# 5_3.net
KiCad netlist of a schematic drawn in Altium Designer
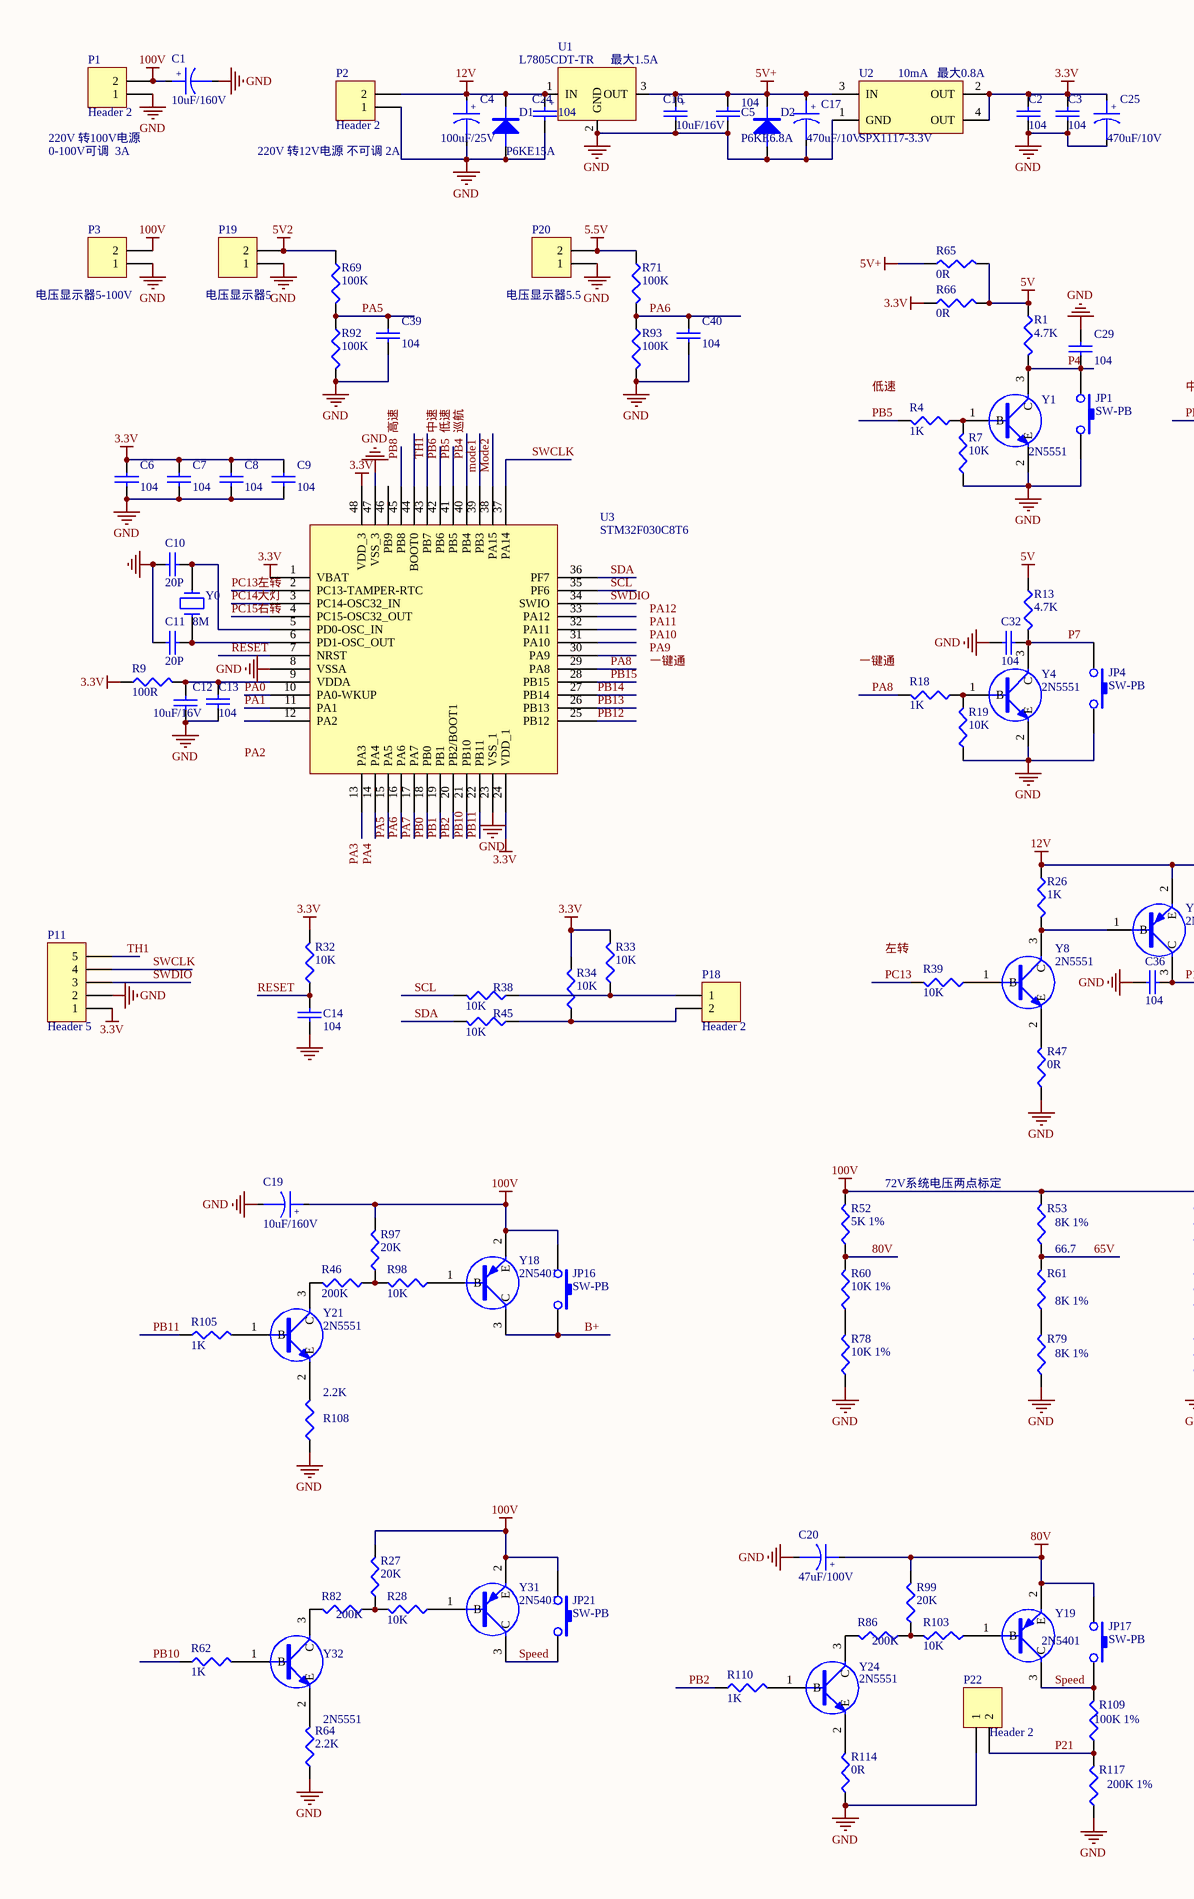
[diagram p0: 仪表自测5.3.SchDoc, left]
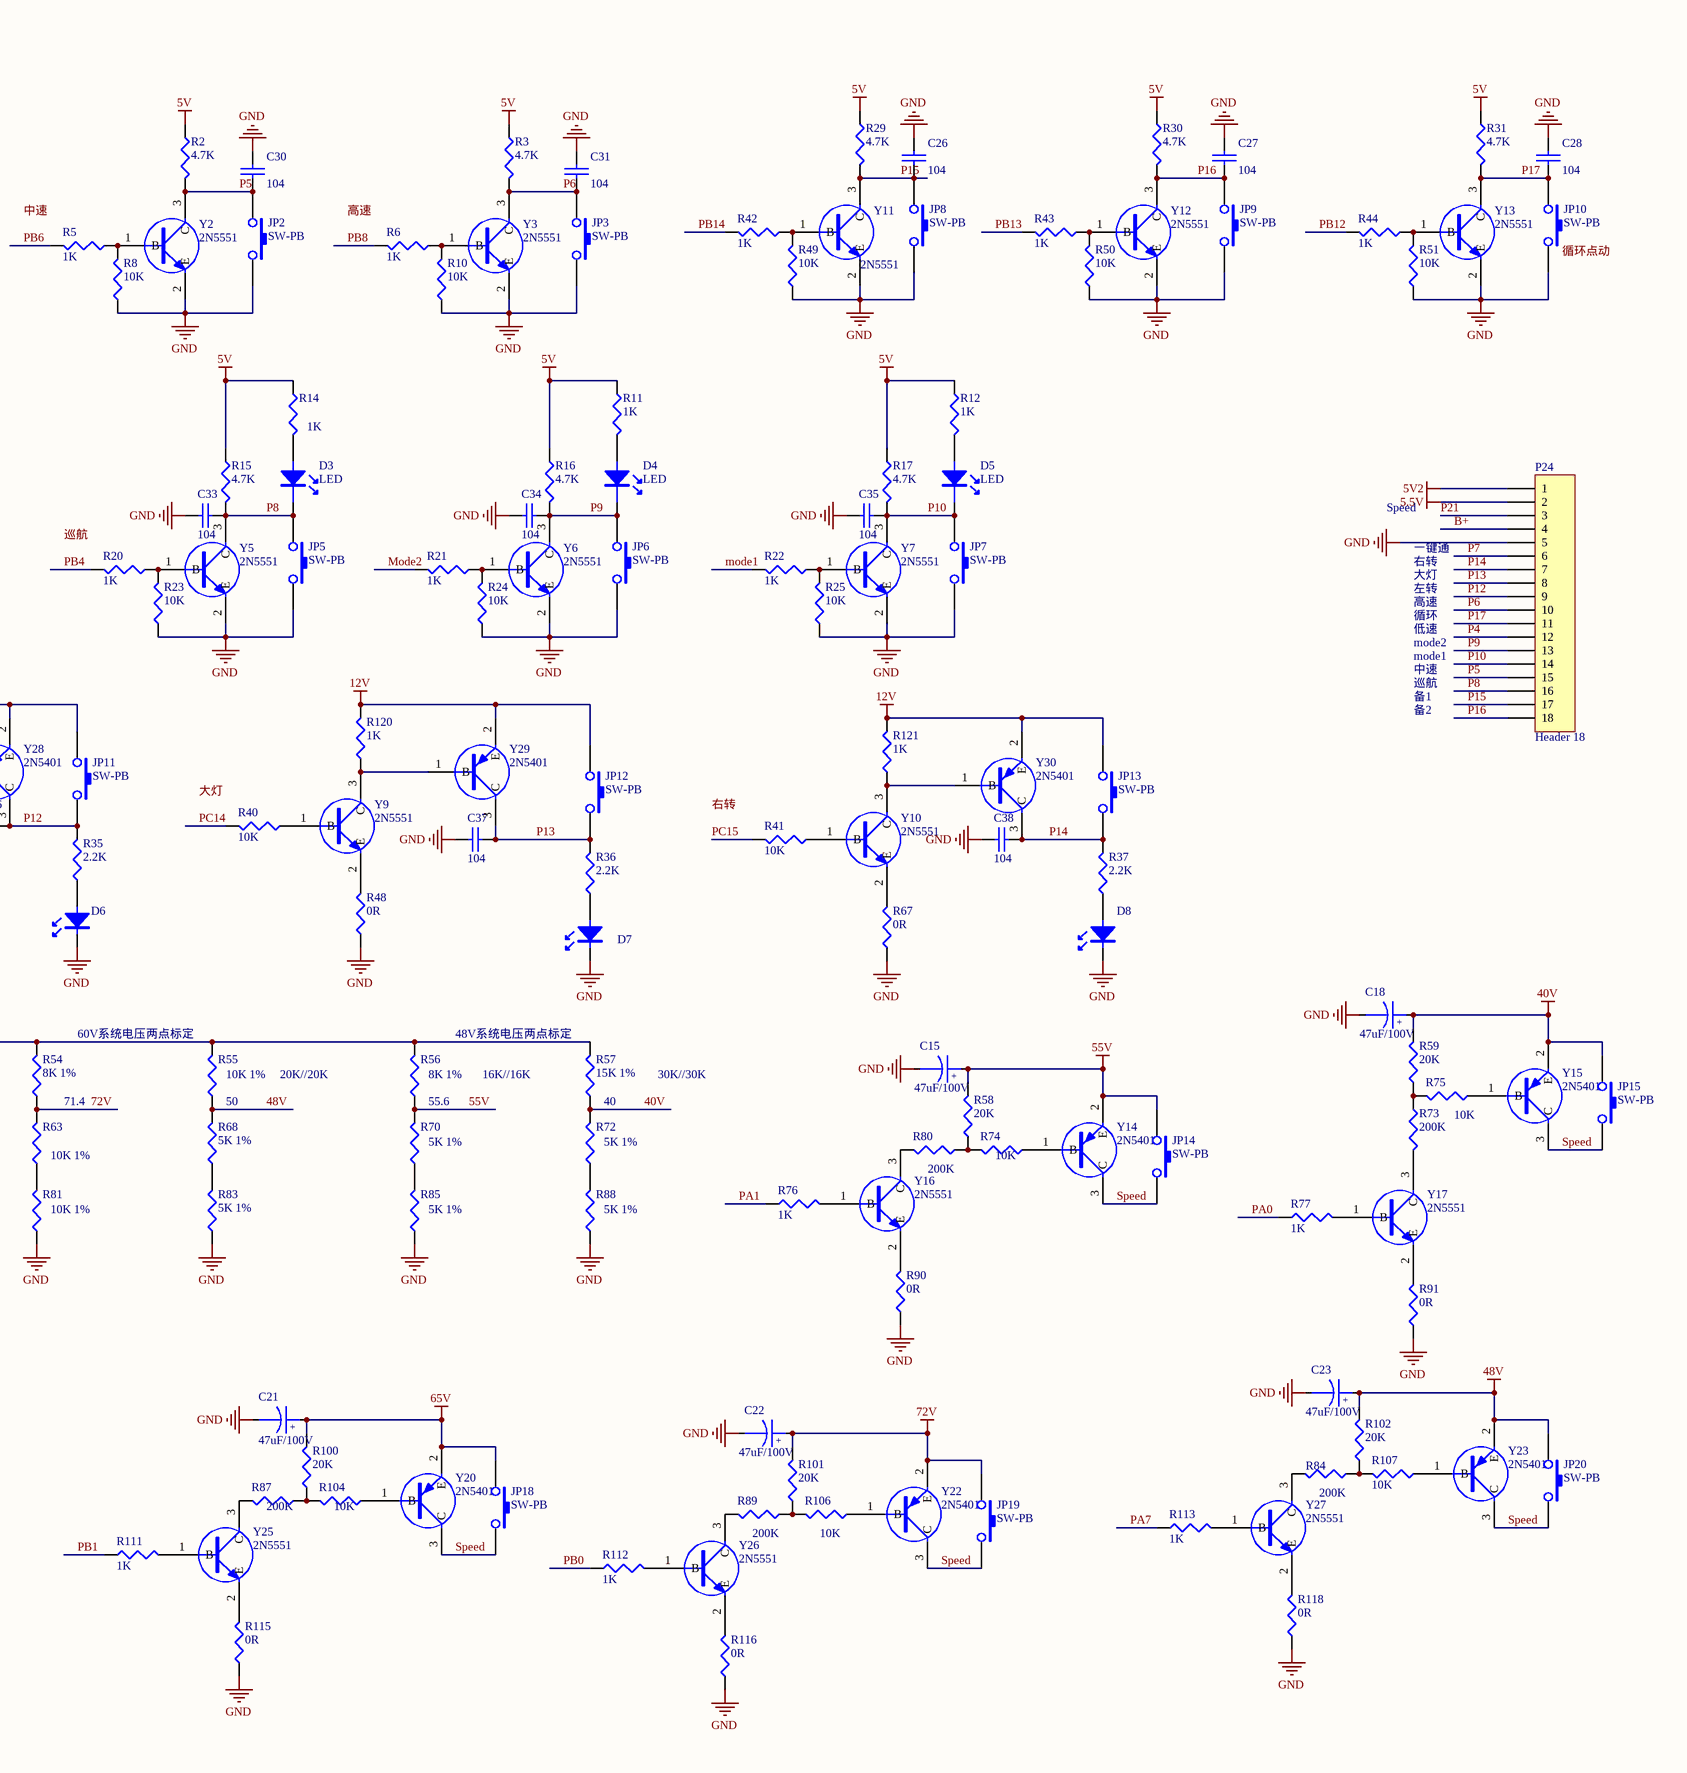
[diagram p1: 仪表自测5.3.SchDoc, right]

(export (version "E")
  (design (tool "Eeschema 10.0.6"))
  (components
    (comp (ref "C1") (value "10uF/160V") (footprint "RB 8*12") (libsource (lib "dsp") (part "Capacitor")))
    (comp (ref "C2") (value "104") (footprint "0805") (libsource (lib "dsp") (part "Cap")))
    (comp (ref "C3") (value "104") (footprint "0805") (libsource (lib "dsp") (part "Cap")))
    (comp (ref "C4") (value "100uF/25V") (footprint "RB.1/.2") (libsource (lib "dsp") (part "Capacitor")))
    (comp (ref "C5") (value "104") (footprint "0805") (libsource (lib "dsp") (part "Cap")))
    (comp (ref "C6")
      (value "104")
      (footprint "0805")
      (description "Capacitor")
      (libsource (lib "*") (part "CAP"))
    )
    (comp (ref "C7")
      (value "104")
      (footprint "0805")
      (description "Capacitor")
      (libsource (lib "*") (part "CAP"))
    )
    (comp (ref "C8")
      (value "104")
      (footprint "0805")
      (description "Capacitor")
      (libsource (lib "*") (part "CAP"))
    )
    (comp (ref "C9")
      (value "104")
      (footprint "0805")
      (description "Capacitor")
      (libsource (lib "*") (part "CAP"))
    )
    (comp (ref "C10")
      (value "20P")
      (footprint "0805")
      (description "Capacitor")
      (libsource (lib "") (part "CAP_1"))
    )
    (comp (ref "C11")
      (value "20P")
      (footprint "0805")
      (description "Capacitor")
      (libsource (lib "") (part "CAP_1"))
    )
    (comp (ref "C12")
      (value "10uF/16V")
      (footprint "1206")
      (description "Capacitor")
      (libsource (lib "*") (part "CAP"))
    )
    (comp (ref "C13")
      (value "104")
      (footprint "0805")
      (description "Capacitor")
      (libsource (lib "*") (part "CAP"))
    )
    (comp (ref "C14") (value "104") (footprint "0805") (libsource (lib "dsp") (part "Cap")))
    (comp (ref "C15") (value "47uF/100V") (footprint "RB 8*12") (libsource (lib "dsp") (part "Capacitor")))
    (comp (ref "C16")
      (value "10uF/16V")
      (footprint "1206")
      (description "Capacitor")
      (libsource (lib "dsp") (part "CAP_1"))
    )
    (comp (ref "C17") (value "470uF/10V") (footprint "RB.1/.2") (libsource (lib "dsp") (part "Capacitor")))
    (comp (ref "C18") (value "47uF/100V") (footprint "RB 8*12") (libsource (lib "dsp") (part "Capacitor")))
    (comp (ref "C19") (value "10uF/160V") (footprint "RB 8*12") (libsource (lib "dsp") (part "Capacitor")))
    (comp (ref "C20") (value "47uF/100V") (footprint "RB 8*12") (libsource (lib "dsp") (part "Capacitor")))
    (comp (ref "C21") (value "47uF/100V") (footprint "RB 8*12") (libsource (lib "dsp") (part "Capacitor")))
    (comp (ref "C22") (value "47uF/100V") (footprint "RB 8*12") (libsource (lib "dsp") (part "Capacitor")))
    (comp (ref "C23") (value "47uF/100V") (footprint "RB 8*12") (libsource (lib "dsp") (part "Capacitor")))
    (comp (ref "C24")
      (value "104")
      (footprint "0805")
      (description "Capacitor")
      (libsource (lib "dsp") (part "CAP_1"))
    )
    (comp (ref "C25") (value "470uF/10V") (footprint "RB.1/.2") (libsource (lib "dsp") (part "Capacitor")))
    (comp (ref "C26") (value "104") (footprint "0805") (libsource (lib "dsp") (part "Cap")))
    (comp (ref "C27") (value "104") (footprint "0805") (libsource (lib "dsp") (part "Cap")))
    (comp (ref "C28") (value "104") (footprint "0805") (libsource (lib "dsp") (part "Cap")))
    (comp (ref "C29") (value "104") (footprint "0805") (libsource (lib "dsp") (part "Cap")))
    (comp (ref "C30") (value "104") (footprint "0805") (libsource (lib "dsp") (part "Cap")))
    (comp (ref "C31") (value "104") (footprint "0805") (libsource (lib "dsp") (part "Cap")))
    (comp (ref "C32") (value "104") (footprint "0805") (libsource (lib "dsp") (part "Cap")))
    (comp (ref "C33") (value "104") (footprint "0805") (libsource (lib "dsp") (part "Cap")))
    (comp (ref "C34") (value "104") (footprint "0805") (libsource (lib "dsp") (part "Cap")))
    (comp (ref "C35") (value "104") (footprint "0805") (libsource (lib "dsp") (part "Cap")))
    (comp (ref "C36") (value "104") (footprint "0805") (libsource (lib "dsp") (part "Cap")))
    (comp (ref "C37") (value "104") (footprint "0805") (libsource (lib "dsp") (part "Cap")))
    (comp (ref "C38") (value "104") (footprint "0805") (libsource (lib "dsp") (part "Cap")))
    (comp (ref "C39")
      (value "104")
      (footprint "0805")
      (description "Capacitor")
      (libsource (lib "*") (part "CAP"))
    )
    (comp (ref "C40")
      (value "104")
      (footprint "0805")
      (description "Capacitor")
      (libsource (lib "*") (part "CAP"))
    )
    (comp (ref "D1")
      (value "P6KE15A")
      (footprint "SMA")
      (description "Diode")
      (libsource (lib "dsp") (part "DIODE"))
    )
    (comp (ref "D2")
      (value "P6KE6.8A")
      (footprint "SMA")
      (description "Diode")
      (libsource (lib "dsp") (part "DIODE"))
    )
    (comp (ref "D3") (value "LED") (footprint "RB.1/.2") (libsource (lib "dsp") (part "LED")))
    (comp (ref "D4") (value "LED") (footprint "RB.1/.2") (libsource (lib "dsp") (part "LED")))
    (comp (ref "D5") (value "LED") (footprint "RB.1/.2") (libsource (lib "dsp") (part "LED")))
    (comp (ref "D6") (value "~") (footprint "RB.1/.2") (libsource (lib "*") (part "LED")))
    (comp (ref "D7") (value "~") (footprint "RB.1/.2") (libsource (lib "*") (part "LED")))
    (comp (ref "D8") (value "~") (footprint "RB.1/.2") (libsource (lib "*") (part "LED")))
    (comp (ref "JP1") (value "SW-PB") (footprint "CON2") (libsource (lib "dsp") (part "SW-PB")))
    (comp (ref "JP2") (value "SW-PB") (footprint "CON2") (libsource (lib "dsp") (part "SW-PB")))
    (comp (ref "JP3") (value "SW-PB") (footprint "CON2") (libsource (lib "dsp") (part "SW-PB")))
    (comp (ref "JP4") (value "SW-PB") (footprint "CON2") (libsource (lib "dsp") (part "SW-PB")))
    (comp (ref "JP5") (value "SW-PB") (footprint "CON2") (libsource (lib "dsp") (part "SW-PB")))
    (comp (ref "JP6") (value "SW-PB") (footprint "CON2") (libsource (lib "dsp") (part "SW-PB")))
    (comp (ref "JP7") (value "SW-PB") (footprint "CON2") (libsource (lib "dsp") (part "SW-PB")))
    (comp (ref "JP8") (value "SW-PB") (footprint "CON2") (libsource (lib "dsp") (part "SW-PB")))
    (comp (ref "JP9") (value "SW-PB") (footprint "CON2") (libsource (lib "dsp") (part "SW-PB")))
    (comp (ref "JP10") (value "SW-PB") (footprint "CON2") (libsource (lib "dsp") (part "SW-PB")))
    (comp (ref "JP11") (value "SW-PB") (footprint "CON2") (libsource (lib "dsp") (part "SW-PB")))
    (comp (ref "JP12") (value "SW-PB") (footprint "CON2") (libsource (lib "dsp") (part "SW-PB")))
    (comp (ref "JP13") (value "SW-PB") (footprint "CON2") (libsource (lib "dsp") (part "SW-PB")))
    (comp (ref "JP14") (value "SW-PB") (footprint "CON2") (libsource (lib "dsp") (part "SW-PB")))
    (comp (ref "JP15") (value "SW-PB") (footprint "CON2") (libsource (lib "dsp") (part "SW-PB")))
    (comp (ref "JP16") (value "SW-PB") (footprint "CON2") (libsource (lib "dsp") (part "SW-PB")))
    (comp (ref "JP17") (value "SW-PB") (footprint "CON2") (libsource (lib "dsp") (part "SW-PB")))
    (comp (ref "JP18") (value "SW-PB") (footprint "CON2") (libsource (lib "dsp") (part "SW-PB")))
    (comp (ref "JP19") (value "SW-PB") (footprint "CON2") (libsource (lib "dsp") (part "SW-PB")))
    (comp (ref "JP20") (value "SW-PB") (footprint "CON2") (libsource (lib "dsp") (part "SW-PB")))
    (comp (ref "JP21") (value "SW-PB") (footprint "CON2") (libsource (lib "dsp") (part "SW-PB")))
    (comp (ref "P1")
      (value "Header 2")
      (footprint "CON2")
      (description "Header, 2-Pin")
      (fields (field (name "PUBLISHER") "Altium Limited"))
      (libsource (lib "Miscellaneous Connectors") (part "Header 2"))
    )
    (comp (ref "P2")
      (value "Header 2")
      (footprint "CON2")
      (description "Header, 2-Pin")
      (fields (field (name "PUBLISHER") "Altium Limited"))
      (libsource (lib "Miscellaneous Connectors") (part "Header 2"))
    )
    (comp (ref "P3")
      (value "电压显示器5-100V")
      (footprint "CON2")
      (description "Header, 2-Pin")
      (fields (field (name "PUBLISHER") "Altium Limited"))
      (libsource (lib "Miscellaneous Connectors") (part "Header 2"))
    )
    (comp (ref "P11")
      (value "Header 5")
      (footprint "HDR1X5")
      (description "Header, 5-Pin")
      (fields (field (name "PUBLISHER") "Altium Limited"))
      (libsource (lib "Miscellaneous Connectors") (part "Header 5"))
    )
    (comp (ref "P18")
      (value "Header 2")
      (footprint "CON2")
      (description "Header, 2-Pin")
      (fields (field (name "PUBLISHER") "Altium Limited"))
      (libsource (lib "") (part "Header 2_1"))
    )
    (comp (ref "P19")
      (value "电压显示器5")
      (footprint "CON2")
      (description "Header, 2-Pin")
      (fields (field (name "PUBLISHER") "Altium Limited"))
      (libsource (lib "Miscellaneous Connectors") (part "Header 2"))
    )
    (comp (ref "P20")
      (value "电压显示器5.5")
      (footprint "CON2")
      (description "Header, 2-Pin")
      (fields (field (name "PUBLISHER") "Altium Limited"))
      (libsource (lib "Miscellaneous Connectors") (part "Header 2"))
    )
    (comp (ref "P22")
      (value "Header 2")
      (footprint "CON2")
      (description "Header, 2-Pin")
      (fields (field (name "PUBLISHER") "Altium Limited"))
      (libsource (lib "dsp") (part "Header 2"))
    )
    (comp (ref "P24")
      (value "Header 18")
      (footprint "SIP18")
      (description "Header, 18-Pin")
      (fields (field (name "PUBLISHER") "Altium Limited"))
      (libsource (lib "dsp") (part "Header 18"))
    )
    (comp (ref "R1") (value "4.7K") (footprint "0805") (libsource (lib "dsp") (part "RES1")))
    (comp (ref "R2") (value "4.7K") (footprint "0805") (libsource (lib "dsp") (part "RES1")))
    (comp (ref "R3") (value "4.7K") (footprint "0805") (libsource (lib "dsp") (part "RES1")))
    (comp (ref "R4") (value "1K") (footprint "0805") (libsource (lib "dsp") (part "RES1")))
    (comp (ref "R5") (value "1K") (footprint "0805") (libsource (lib "dsp") (part "RES1")))
    (comp (ref "R6") (value "1K") (footprint "0805") (libsource (lib "dsp") (part "RES1")))
    (comp (ref "R7") (value "10K") (footprint "0805") (libsource (lib "dsp") (part "RES1")))
    (comp (ref "R8") (value "10K") (footprint "0805") (libsource (lib "dsp") (part "RES1")))
    (comp (ref "R9") (value "100R") (footprint "0805") (libsource (lib "dsp") (part "RES1")))
    (comp (ref "R10") (value "10K") (footprint "0805") (libsource (lib "dsp") (part "RES1")))
    (comp (ref "R11") (value "1K") (footprint "0805") (libsource (lib "dsp") (part "RES1")))
    (comp (ref "R12") (value "1K") (footprint "0805") (libsource (lib "dsp") (part "RES1")))
    (comp (ref "R13") (value "4.7K") (footprint "0805") (libsource (lib "dsp") (part "RES1")))
    (comp (ref "R14") (value "1K") (footprint "0805") (libsource (lib "dsp") (part "RES1")))
    (comp (ref "R15") (value "4.7K") (footprint "0805") (libsource (lib "dsp") (part "RES1")))
    (comp (ref "R16") (value "4.7K") (footprint "0805") (libsource (lib "dsp") (part "RES1")))
    (comp (ref "R17") (value "4.7K") (footprint "0805") (libsource (lib "dsp") (part "RES1")))
    (comp (ref "R18") (value "1K") (footprint "0805") (libsource (lib "dsp") (part "RES1")))
    (comp (ref "R19") (value "10K") (footprint "0805") (libsource (lib "dsp") (part "RES1")))
    (comp (ref "R20") (value "1K") (footprint "0805") (libsource (lib "dsp") (part "RES1")))
    (comp (ref "R21") (value "1K") (footprint "0805") (libsource (lib "dsp") (part "RES1")))
    (comp (ref "R22") (value "1K") (footprint "0805") (libsource (lib "dsp") (part "RES1")))
    (comp (ref "R23") (value "10K") (footprint "0805") (libsource (lib "dsp") (part "RES1")))
    (comp (ref "R24") (value "10K") (footprint "0805") (libsource (lib "dsp") (part "RES1")))
    (comp (ref "R25") (value "10K") (footprint "0805") (libsource (lib "dsp") (part "RES1")))
    (comp (ref "R26") (value "1K") (footprint "0805") (libsource (lib "dsp") (part "RES1")))
    (comp (ref "R27") (value "20K") (footprint "0805") (libsource (lib "dsp") (part "RES1")))
    (comp (ref "R28") (value "10K") (footprint "0805") (libsource (lib "dsp") (part "RES1")))
    (comp (ref "R29") (value "4.7K") (footprint "0805") (libsource (lib "dsp") (part "RES1")))
    (comp (ref "R30") (value "4.7K") (footprint "0805") (libsource (lib "dsp") (part "RES1")))
    (comp (ref "R31") (value "4.7K") (footprint "0805") (libsource (lib "dsp") (part "RES1")))
    (comp (ref "R32") (value "10K") (footprint "0805") (libsource (lib "dsp") (part "RES1")))
    (comp (ref "R33") (value "10K") (footprint "0805") (libsource (lib "dsp") (part "RES1")))
    (comp (ref "R34") (value "10K") (footprint "0805") (libsource (lib "dsp") (part "RES1")))
    (comp (ref "R35") (value "2.2K") (footprint "0805") (libsource (lib "dsp") (part "RES1")))
    (comp (ref "R36") (value "2.2K") (footprint "0805") (libsource (lib "dsp") (part "RES1")))
    (comp (ref "R37") (value "2.2K") (footprint "0805") (libsource (lib "dsp") (part "RES1")))
    (comp (ref "R38") (value "10K") (footprint "0805") (libsource (lib "dsp") (part "RES1")))
    (comp (ref "R39") (value "10K") (footprint "0805") (libsource (lib "dsp") (part "RES1")))
    (comp (ref "R40") (value "10K") (footprint "0805") (libsource (lib "dsp") (part "RES1")))
    (comp (ref "R41") (value "10K") (footprint "0805") (libsource (lib "dsp") (part "RES1")))
    (comp (ref "R42") (value "1K") (footprint "0805") (libsource (lib "dsp") (part "RES1")))
    (comp (ref "R43") (value "1K") (footprint "0805") (libsource (lib "dsp") (part "RES1")))
    (comp (ref "R44") (value "1K") (footprint "0805") (libsource (lib "dsp") (part "RES1")))
    (comp (ref "R45") (value "10K") (footprint "0805") (libsource (lib "dsp") (part "RES1")))
    (comp (ref "R46") (value "200K") (footprint "0805") (libsource (lib "dsp") (part "RES1")))
    (comp (ref "R47") (value "0R") (footprint "0805") (libsource (lib "dsp") (part "RES1")))
    (comp (ref "R48") (value "0R") (footprint "0805") (libsource (lib "dsp") (part "RES1")))
    (comp (ref "R49") (value "10K") (footprint "0805") (libsource (lib "dsp") (part "RES1")))
    (comp (ref "R50") (value "10K") (footprint "0805") (libsource (lib "dsp") (part "RES1")))
    (comp (ref "R51") (value "10K") (footprint "0805") (libsource (lib "dsp") (part "RES1")))
    (comp (ref "R52") (value "5K 1%") (footprint "1206") (libsource (lib "dsp") (part "RES1")))
    (comp (ref "R53") (value "8K 1%") (footprint "1206") (libsource (lib "dsp") (part "RES1")))
    (comp (ref "R54") (value "8K 1%") (footprint "1206") (libsource (lib "dsp") (part "RES1")))
    (comp (ref "R55") (value "10K 1%") (footprint "1206") (libsource (lib "dsp") (part "RES1")))
    (comp (ref "R56") (value "8K 1%") (footprint "1206") (libsource (lib "dsp") (part "RES1")))
    (comp (ref "R57") (value "15K 1%") (footprint "1206") (libsource (lib "dsp") (part "RES1")))
    (comp (ref "R58") (value "20K") (footprint "0805") (libsource (lib "dsp") (part "RES1")))
    (comp (ref "R59") (value "20K") (footprint "0805") (libsource (lib "dsp") (part "RES1")))
    (comp (ref "R60") (value "10K 1%") (footprint "1206") (libsource (lib "dsp") (part "RES1")))
    (comp (ref "R61") (value "8K 1%") (footprint "1206") (libsource (lib "dsp") (part "RES1")))
    (comp (ref "R62") (value "1K") (footprint "0805") (libsource (lib "dsp") (part "RES1")))
    (comp (ref "R63") (value "10K 1%") (footprint "1206") (libsource (lib "dsp") (part "RES1")))
    (comp (ref "R64") (value "2.2K") (footprint "0805") (libsource (lib "dsp") (part "RES1")))
    (comp (ref "R65") (value "0R") (footprint "0805") (libsource (lib "dsp") (part "RES1")))
    (comp (ref "R66") (value "0R") (footprint "0805") (libsource (lib "dsp") (part "RES1")))
    (comp (ref "R67") (value "0R") (footprint "0805") (libsource (lib "dsp") (part "RES1")))
    (comp (ref "R68") (value "5K 1%") (footprint "1206") (libsource (lib "dsp") (part "RES1")))
    (comp (ref "R69") (value "100K") (footprint "0805") (libsource (lib "dsp") (part "RES1")))
    (comp (ref "R70") (value "5K 1%") (footprint "1206") (libsource (lib "dsp") (part "RES1")))
    (comp (ref "R71") (value "100K") (footprint "0805") (libsource (lib "dsp") (part "RES1")))
    (comp (ref "R72") (value "5K 1%") (footprint "1206") (libsource (lib "dsp") (part "RES1")))
    (comp (ref "R73") (value "200K") (footprint "0805") (libsource (lib "dsp") (part "RES1")))
    (comp (ref "R74") (value "10K") (footprint "0805") (libsource (lib "dsp") (part "RES1")))
    (comp (ref "R75") (value "10K") (footprint "0805") (libsource (lib "dsp") (part "RES1")))
    (comp (ref "R76") (value "1K") (footprint "0805") (libsource (lib "dsp") (part "RES1")))
    (comp (ref "R77") (value "1K") (footprint "0805") (libsource (lib "dsp") (part "RES1")))
    (comp (ref "R78") (value "10K 1%") (footprint "1206") (libsource (lib "dsp") (part "RES1")))
    (comp (ref "R79") (value "8K 1%") (footprint "1206") (libsource (lib "dsp") (part "RES1")))
    (comp (ref "R80") (value "200K") (footprint "0805") (libsource (lib "dsp") (part "RES1")))
    (comp (ref "R81") (value "10K 1%") (footprint "1206") (libsource (lib "dsp") (part "RES1")))
    (comp (ref "R82") (value "200K") (footprint "0805") (libsource (lib "dsp") (part "RES1")))
    (comp (ref "R83") (value "5K 1%") (footprint "1206") (libsource (lib "dsp") (part "RES1")))
    (comp (ref "R84") (value "200K") (footprint "0805") (libsource (lib "dsp") (part "RES1")))
    (comp (ref "R85") (value "5K 1%") (footprint "1206") (libsource (lib "dsp") (part "RES1")))
    (comp (ref "R86") (value "200K") (footprint "0805") (libsource (lib "dsp") (part "RES1")))
    (comp (ref "R87") (value "200K") (footprint "0805") (libsource (lib "dsp") (part "RES1")))
    (comp (ref "R88") (value "5K 1%") (footprint "1206") (libsource (lib "dsp") (part "RES1")))
    (comp (ref "R89") (value "200K") (footprint "0805") (libsource (lib "dsp") (part "RES1")))
    (comp (ref "R90") (value "0R") (footprint "0805") (libsource (lib "dsp") (part "RES1")))
    (comp (ref "R91") (value "0R") (footprint "0805") (libsource (lib "dsp") (part "RES1")))
    (comp (ref "R92") (value "100K") (footprint "0805") (libsource (lib "dsp") (part "RES1")))
    (comp (ref "R93") (value "100K") (footprint "0805") (libsource (lib "dsp") (part "RES1")))
    (comp (ref "R97") (value "20K") (footprint "0805") (libsource (lib "dsp") (part "RES1")))
    (comp (ref "R98") (value "10K") (footprint "0805") (libsource (lib "dsp") (part "RES1")))
    (comp (ref "R99") (value "20K") (footprint "0805") (libsource (lib "dsp") (part "RES1")))
    (comp (ref "R100") (value "20K") (footprint "0805") (libsource (lib "dsp") (part "RES1")))
    (comp (ref "R101") (value "20K") (footprint "0805") (libsource (lib "dsp") (part "RES1")))
    (comp (ref "R102") (value "20K") (footprint "0805") (libsource (lib "dsp") (part "RES1")))
    (comp (ref "R103") (value "10K") (footprint "0805") (libsource (lib "dsp") (part "RES1")))
    (comp (ref "R104") (value "10K") (footprint "0805") (libsource (lib "dsp") (part "RES1")))
    (comp (ref "R105") (value "1K") (footprint "0805") (libsource (lib "dsp") (part "RES1")))
    (comp (ref "R106") (value "10K") (footprint "0805") (libsource (lib "dsp") (part "RES1")))
    (comp (ref "R107") (value "10K") (footprint "0805") (libsource (lib "dsp") (part "RES1")))
    (comp (ref "R108") (value "2.2K") (footprint "0805") (libsource (lib "dsp") (part "RES1")))
    (comp (ref "R109") (value "100K 1%") (footprint "2512") (libsource (lib "dsp") (part "RES1")))
    (comp (ref "R110") (value "1K") (footprint "0805") (libsource (lib "dsp") (part "RES1")))
    (comp (ref "R111") (value "1K") (footprint "0805") (libsource (lib "dsp") (part "RES1")))
    (comp (ref "R112") (value "1K") (footprint "0805") (libsource (lib "dsp") (part "RES1")))
    (comp (ref "R113") (value "1K") (footprint "0805") (libsource (lib "dsp") (part "RES1")))
    (comp (ref "R114") (value "0R") (footprint "0805") (libsource (lib "dsp") (part "RES1")))
    (comp (ref "R115") (value "0R") (footprint "0805") (libsource (lib "dsp") (part "RES1")))
    (comp (ref "R116") (value "0R") (footprint "0805") (libsource (lib "dsp") (part "RES1")))
    (comp (ref "R117") (value "200K 1%") (footprint "2512") (libsource (lib "dsp") (part "RES1")))
    (comp (ref "R118") (value "0R") (footprint "0805") (libsource (lib "dsp") (part "RES1")))
    (comp (ref "R120") (value "1K") (footprint "0805") (libsource (lib "dsp") (part "RES1")))
    (comp (ref "R121") (value "1K") (footprint "0805") (libsource (lib "dsp") (part "RES1")))
    (comp (ref "U1") (value "L7805CDT-TR") (footprint "TO-252") (libsource (lib "*") (part "IC3")))
    (comp (ref "U2")
      (value "SPX1117-3.3V")
      (footprint "SOT-223")
      (libsource (lib "dsp") (part "SPX1117-3.3V"))
    )
    (comp (ref "U3")
      (value "STM32F030C8T6")
      (footprint "STM32F103-LQFP48")
      (libsource (lib "dsp") (part "STM32F030C8T6"))
    )
    (comp (ref "Y0")
      (value "8M")
      (footprint "RAD0.2")
      (description "Crystal")
      (libsource (lib "*") (part "CRYSTAL"))
    )
    (comp (ref "Y1")
      (value "2N5551")
      (footprint "SOT-23")
      (description "NPN SOT-23")
      (libsource (lib "dsp") (part "NPN SOT-23"))
    )
    (comp (ref "Y2")
      (value "2N5551")
      (footprint "SOT-23")
      (description "NPN SOT-23")
      (libsource (lib "dsp") (part "NPN SOT-23"))
    )
    (comp (ref "Y3")
      (value "2N5551")
      (footprint "SOT-23")
      (description "NPN SOT-23")
      (libsource (lib "dsp") (part "NPN SOT-23"))
    )
    (comp (ref "Y4")
      (value "2N5551")
      (footprint "SOT-23")
      (description "NPN SOT-23")
      (libsource (lib "dsp") (part "NPN SOT-23"))
    )
    (comp (ref "Y5")
      (value "2N5551")
      (footprint "SOT-23")
      (description "NPN SOT-23")
      (libsource (lib "dsp") (part "NPN SOT-23"))
    )
    (comp (ref "Y6")
      (value "2N5551")
      (footprint "SOT-23")
      (description "NPN SOT-23")
      (libsource (lib "dsp") (part "NPN SOT-23"))
    )
    (comp (ref "Y7")
      (value "2N5551")
      (footprint "SOT-23")
      (description "NPN SOT-23")
      (libsource (lib "dsp") (part "NPN SOT-23"))
    )
    (comp (ref "Y8")
      (value "2N5551")
      (footprint "SOT-23")
      (description "NPN SOT-23")
      (libsource (lib "dsp") (part "NPN SOT-23"))
    )
    (comp (ref "Y9")
      (value "2N5551")
      (footprint "SOT-23")
      (description "NPN SOT-23")
      (libsource (lib "dsp") (part "NPN SOT-23"))
    )
    (comp (ref "Y10")
      (value "2N5551")
      (footprint "SOT-23")
      (description "NPN SOT-23")
      (libsource (lib "dsp") (part "NPN SOT-23"))
    )
    (comp (ref "Y11")
      (value "2N5551")
      (footprint "SOT-23")
      (description "NPN SOT-23")
      (libsource (lib "dsp") (part "NPN SOT-23"))
    )
    (comp (ref "Y12")
      (value "2N5551")
      (footprint "SOT-23")
      (description "NPN SOT-23")
      (libsource (lib "dsp") (part "NPN SOT-23"))
    )
    (comp (ref "Y13")
      (value "2N5551")
      (footprint "SOT-23")
      (description "NPN SOT-23")
      (libsource (lib "dsp") (part "NPN SOT-23"))
    )
    (comp (ref "Y14")
      (value "2N5401")
      (footprint "SOT-23")
      (description "PNP SOT-23")
      (libsource (lib "dsp") (part "PNP SOT-23"))
    )
    (comp (ref "Y15")
      (value "2N5401")
      (footprint "SOT-23")
      (description "PNP SOT-23")
      (libsource (lib "dsp") (part "PNP SOT-23"))
    )
    (comp (ref "Y16")
      (value "2N5551")
      (footprint "SOT-23")
      (description "NPN SOT-23")
      (libsource (lib "dsp") (part "NPN SOT-23"))
    )
    (comp (ref "Y17")
      (value "2N5551")
      (footprint "SOT-23")
      (description "NPN SOT-23")
      (libsource (lib "dsp") (part "NPN SOT-23"))
    )
    (comp (ref "Y18")
      (value "2N5401")
      (footprint "SOT-23")
      (description "PNP SOT-23")
      (libsource (lib "dsp") (part "PNP SOT-23"))
    )
    (comp (ref "Y19")
      (value "2N5401")
      (footprint "SOT-23")
      (description "PNP SOT-23")
      (libsource (lib "dsp") (part "PNP SOT-23"))
    )
    (comp (ref "Y20")
      (value "2N5401")
      (footprint "SOT-23")
      (description "PNP SOT-23")
      (libsource (lib "dsp") (part "PNP SOT-23"))
    )
    (comp (ref "Y21")
      (value "2N5551")
      (footprint "SOT-23")
      (description "NPN SOT-23")
      (libsource (lib "dsp") (part "NPN SOT-23"))
    )
    (comp (ref "Y22")
      (value "2N5401")
      (footprint "SOT-23")
      (description "PNP SOT-23")
      (libsource (lib "dsp") (part "PNP SOT-23"))
    )
    (comp (ref "Y23")
      (value "2N5401")
      (footprint "SOT-23")
      (description "PNP SOT-23")
      (libsource (lib "dsp") (part "PNP SOT-23"))
    )
    (comp (ref "Y24")
      (value "2N5551")
      (footprint "SOT-23")
      (description "NPN SOT-23")
      (libsource (lib "dsp") (part "NPN SOT-23"))
    )
    (comp (ref "Y25")
      (value "2N5551")
      (footprint "SOT-23")
      (description "NPN SOT-23")
      (libsource (lib "dsp") (part "NPN SOT-23"))
    )
    (comp (ref "Y26")
      (value "2N5551")
      (footprint "SOT-23")
      (description "NPN SOT-23")
      (libsource (lib "dsp") (part "NPN SOT-23"))
    )
    (comp (ref "Y27")
      (value "2N5551")
      (footprint "SOT-23")
      (description "NPN SOT-23")
      (libsource (lib "dsp") (part "NPN SOT-23"))
    )
    (comp (ref "Y28")
      (value "2N5401")
      (footprint "SOT-23")
      (description "PNP SOT-23")
      (libsource (lib "dsp") (part "PNP SOT-23"))
    )
    (comp (ref "Y29")
      (value "2N5401")
      (footprint "SOT-23")
      (description "PNP SOT-23")
      (libsource (lib "dsp") (part "PNP SOT-23"))
    )
    (comp (ref "Y30")
      (value "2N5401")
      (footprint "SOT-23")
      (description "PNP SOT-23")
      (libsource (lib "dsp") (part "PNP SOT-23"))
    )
    (comp (ref "Y31")
      (value "2N5401")
      (footprint "SOT-23")
      (description "PNP SOT-23")
      (libsource (lib "dsp") (part "PNP SOT-23"))
    )
    (comp (ref "Y32")
      (value "2N5551")
      (footprint "SOT-23")
      (description "NPN SOT-23")
      (libsource (lib "dsp") (part "NPN SOT-23"))
    )
  )
  (nets
    (net (code "1") (name "/B+") (class "Default")
      (node (ref "JP16") (pin "2") (pinfunction "2_2") (pintype "passive"))
      (node (ref "P24") (pin "4") (pinfunction "4_4") (pintype "passive"))
      (node (ref "Y18") (pin "3") (pinfunction "C_3") (pintype "passive"))
    )
    (net (code "2") (name "/Mode2") (class "Default")
      (node (ref "R21") (pin "2") (pinfunction "2_2") (pintype "passive"))
      (node (ref "U3") (pin "38") (pinfunction "PA15_38") (pintype "passive"))
    )
    (net (code "3") (name "/P4") (class "Default")
      (node (ref "C29") (pin "2") (pinfunction "2_2") (pintype "passive"))
      (node (ref "JP1") (pin "1") (pinfunction "1_1") (pintype "passive"))
      (node (ref "P24") (pin "12") (pinfunction "12_12") (pintype "passive"))
      (node (ref "R1") (pin "2") (pinfunction "2_2") (pintype "passive"))
      (node (ref "Y1") (pin "3") (pinfunction "C_3") (pintype "passive"))
    )
    (net (code "4") (name "/P5") (class "Default")
      (node (ref "C30") (pin "2") (pinfunction "2_2") (pintype "passive"))
      (node (ref "JP2") (pin "1") (pinfunction "1_1") (pintype "passive"))
      (node (ref "P24") (pin "15") (pinfunction "15_15") (pintype "passive"))
      (node (ref "R2") (pin "2") (pinfunction "2_2") (pintype "passive"))
      (node (ref "Y2") (pin "3") (pinfunction "C_3") (pintype "passive"))
    )
    (net (code "5") (name "/P6") (class "Default")
      (node (ref "C31") (pin "2") (pinfunction "2_2") (pintype "passive"))
      (node (ref "JP3") (pin "1") (pinfunction "1_1") (pintype "passive"))
      (node (ref "P24") (pin "10") (pinfunction "10_10") (pintype "passive"))
      (node (ref "R3") (pin "2") (pinfunction "2_2") (pintype "passive"))
      (node (ref "Y3") (pin "3") (pinfunction "C_3") (pintype "passive"))
    )
    (net (code "6") (name "/P7") (class "Default")
      (node (ref "C32") (pin "2") (pinfunction "2_2") (pintype "passive"))
      (node (ref "JP4") (pin "1") (pinfunction "1_1") (pintype "passive"))
      (node (ref "P24") (pin "6") (pinfunction "6_6") (pintype "passive"))
      (node (ref "R13") (pin "2") (pinfunction "2_2") (pintype "passive"))
      (node (ref "Y4") (pin "3") (pinfunction "C_3") (pintype "passive"))
    )
    (net (code "7") (name "/P8") (class "Default")
      (node (ref "C33") (pin "2") (pinfunction "2_2") (pintype "passive"))
      (node (ref "D3") (pin "2") (pinfunction "2_2") (pintype "passive"))
      (node (ref "JP5") (pin "1") (pinfunction "1_1") (pintype "passive"))
      (node (ref "P24") (pin "16") (pinfunction "16_16") (pintype "passive"))
      (node (ref "R15") (pin "2") (pinfunction "2_2") (pintype "passive"))
      (node (ref "Y5") (pin "3") (pinfunction "C_3") (pintype "passive"))
    )
    (net (code "8") (name "/P9") (class "Default")
      (node (ref "C34") (pin "2") (pinfunction "2_2") (pintype "passive"))
      (node (ref "D4") (pin "2") (pinfunction "2_2") (pintype "passive"))
      (node (ref "JP6") (pin "1") (pinfunction "1_1") (pintype "passive"))
      (node (ref "P24") (pin "13") (pinfunction "13_13") (pintype "passive"))
      (node (ref "R16") (pin "2") (pinfunction "2_2") (pintype "passive"))
      (node (ref "Y6") (pin "3") (pinfunction "C_3") (pintype "passive"))
    )
    (net (code "9") (name "/P10") (class "Default")
      (node (ref "C35") (pin "2") (pinfunction "2_2") (pintype "passive"))
      (node (ref "D5") (pin "2") (pinfunction "2_2") (pintype "passive"))
      (node (ref "JP7") (pin "1") (pinfunction "1_1") (pintype "passive"))
      (node (ref "P24") (pin "14") (pinfunction "14_14") (pintype "passive"))
      (node (ref "R17") (pin "2") (pinfunction "2_2") (pintype "passive"))
      (node (ref "Y7") (pin "3") (pinfunction "C_3") (pintype "passive"))
    )
    (net (code "10") (name "/P12") (class "Default")
      (node (ref "C36") (pin "2") (pinfunction "2_2") (pintype "passive"))
      (node (ref "JP11") (pin "2") (pinfunction "2_2") (pintype "passive"))
      (node (ref "P24") (pin "9") (pinfunction "9_9") (pintype "passive"))
      (node (ref "R35") (pin "2") (pinfunction "2_2") (pintype "passive"))
      (node (ref "Y28") (pin "3") (pinfunction "C_3") (pintype "passive"))
    )
    (net (code "11") (name "/P13") (class "Default")
      (node (ref "C37") (pin "2") (pinfunction "2_2") (pintype "passive"))
      (node (ref "JP12") (pin "2") (pinfunction "2_2") (pintype "passive"))
      (node (ref "P24") (pin "8") (pinfunction "8_8") (pintype "passive"))
      (node (ref "R36") (pin "2") (pinfunction "2_2") (pintype "passive"))
      (node (ref "Y29") (pin "3") (pinfunction "C_3") (pintype "passive"))
    )
    (net (code "12") (name "/P14") (class "Default")
      (node (ref "C38") (pin "2") (pinfunction "2_2") (pintype "passive"))
      (node (ref "JP13") (pin "2") (pinfunction "2_2") (pintype "passive"))
      (node (ref "P24") (pin "7") (pinfunction "7_7") (pintype "passive"))
      (node (ref "R37") (pin "2") (pinfunction "2_2") (pintype "passive"))
      (node (ref "Y30") (pin "3") (pinfunction "C_3") (pintype "passive"))
    )
    (net (code "13") (name "/P15") (class "Default")
      (node (ref "C26") (pin "2") (pinfunction "2_2") (pintype "passive"))
      (node (ref "JP8") (pin "1") (pinfunction "1_1") (pintype "passive"))
      (node (ref "P24") (pin "17") (pinfunction "17_17") (pintype "passive"))
      (node (ref "R29") (pin "2") (pinfunction "2_2") (pintype "passive"))
      (node (ref "Y11") (pin "3") (pinfunction "C_3") (pintype "passive"))
    )
    (net (code "14") (name "/P16") (class "Default")
      (node (ref "C27") (pin "2") (pinfunction "2_2") (pintype "passive"))
      (node (ref "JP9") (pin "1") (pinfunction "1_1") (pintype "passive"))
      (node (ref "P24") (pin "18") (pinfunction "18_18") (pintype "passive"))
      (node (ref "R30") (pin "2") (pinfunction "2_2") (pintype "passive"))
      (node (ref "Y12") (pin "3") (pinfunction "C_3") (pintype "passive"))
    )
    (net (code "15") (name "/P17") (class "Default")
      (node (ref "C28") (pin "2") (pinfunction "2_2") (pintype "passive"))
      (node (ref "JP10") (pin "1") (pinfunction "1_1") (pintype "passive"))
      (node (ref "P24") (pin "11") (pinfunction "11_11") (pintype "passive"))
      (node (ref "R31") (pin "2") (pinfunction "2_2") (pintype "passive"))
      (node (ref "Y13") (pin "3") (pinfunction "C_3") (pintype "passive"))
    )
    (net (code "16") (name "/P21") (class "Default")
      (node (ref "P22") (pin "2") (pinfunction "2_2") (pintype "passive"))
      (node (ref "P24") (pin "3") (pinfunction "3_3") (pintype "passive"))
      (node (ref "R109") (pin "1") (pinfunction "1_1") (pintype "passive"))
      (node (ref "R117") (pin "2") (pinfunction "2_2") (pintype "passive"))
    )
    (net (code "17") (name "/PA0") (class "Default")
      (node (ref "R77") (pin "1") (pinfunction "1_1") (pintype "passive"))
      (node (ref "U3") (pin "10") (pinfunction "PA0-WKUP_10") (pintype "passive"))
    )
    (net (code "18") (name "/PA1") (class "Default")
      (node (ref "R76") (pin "1") (pinfunction "1_1") (pintype "passive"))
      (node (ref "U3") (pin "11") (pinfunction "PA1_11") (pintype "passive"))
    )
    (net (code "22") (name "/PA5") (class "Default")
      (node (ref "C39") (pin "2") (pinfunction "2_2") (pintype "passive"))
      (node (ref "R69") (pin "2") (pinfunction "2_2") (pintype "passive"))
      (node (ref "R92") (pin "1") (pinfunction "1_1") (pintype "passive"))
      (node (ref "U3") (pin "15") (pinfunction "PA5_15") (pintype "passive"))
    )
    (net (code "23") (name "/PA6") (class "Default")
      (node (ref "C40") (pin "2") (pinfunction "2_2") (pintype "passive"))
      (node (ref "R71") (pin "2") (pinfunction "2_2") (pintype "passive"))
      (node (ref "R93") (pin "1") (pinfunction "1_1") (pintype "passive"))
      (node (ref "U3") (pin "16") (pinfunction "PA6_16") (pintype "passive"))
    )
    (net (code "24") (name "/PA7") (class "Default")
      (node (ref "R113") (pin "1") (pinfunction "1_1") (pintype "passive"))
      (node (ref "U3") (pin "17") (pinfunction "PA7_17") (pintype "passive"))
    )
    (net (code "25") (name "/PA8") (class "Default")
      (node (ref "R18") (pin "2") (pinfunction "2_2") (pintype "passive"))
      (node (ref "U3") (pin "29") (pinfunction "PA8_29") (pintype "passive"))
    )
    (net (code "30") (name "/PB0") (class "Default")
      (node (ref "R112") (pin "1") (pinfunction "1_1") (pintype "passive"))
      (node (ref "U3") (pin "18") (pinfunction "PB0_18") (pintype "passive"))
    )
    (net (code "31") (name "/PB1") (class "Default")
      (node (ref "R111") (pin "1") (pinfunction "1_1") (pintype "passive"))
      (node (ref "U3") (pin "19") (pinfunction "PB1_19") (pintype "passive"))
    )
    (net (code "32") (name "/PB2") (class "Default")
      (node (ref "R110") (pin "1") (pinfunction "1_1") (pintype "passive"))
      (node (ref "U3") (pin "20") (pinfunction "PB2/BOOT1_20") (pintype "passive"))
    )
    (net (code "33") (name "/PB4") (class "Default")
      (node (ref "R20") (pin "2") (pinfunction "2_2") (pintype "passive"))
      (node (ref "U3") (pin "40") (pinfunction "PB4_40") (pintype "passive"))
    )
    (net (code "34") (name "/PB5") (class "Default")
      (node (ref "R4") (pin "2") (pinfunction "2_2") (pintype "passive"))
      (node (ref "U3") (pin "41") (pinfunction "PB5_41") (pintype "passive"))
    )
    (net (code "35") (name "/PB6") (class "Default")
      (node (ref "R5") (pin "2") (pinfunction "2_2") (pintype "passive"))
      (node (ref "U3") (pin "42") (pinfunction "PB6_42") (pintype "passive"))
    )
    (net (code "36") (name "/PB8") (class "Default")
      (node (ref "R6") (pin "2") (pinfunction "2_2") (pintype "passive"))
      (node (ref "U3") (pin "45") (pinfunction "PB8_45") (pintype "passive"))
    )
    (net (code "37") (name "/PB10") (class "Default")
      (node (ref "R62") (pin "1") (pinfunction "1_1") (pintype "passive"))
      (node (ref "U3") (pin "21") (pinfunction "PB10_21") (pintype "passive"))
    )
    (net (code "38") (name "/PB11") (class "Default")
      (node (ref "R105") (pin "1") (pinfunction "1_1") (pintype "passive"))
      (node (ref "U3") (pin "22") (pinfunction "PB11_22") (pintype "passive"))
    )
    (net (code "39") (name "/PB12") (class "Default")
      (node (ref "R44") (pin "2") (pinfunction "2_2") (pintype "passive"))
      (node (ref "U3") (pin "25") (pinfunction "PB12_25") (pintype "passive"))
    )
    (net (code "40") (name "/PB13") (class "Default")
      (node (ref "R43") (pin "2") (pinfunction "2_2") (pintype "passive"))
      (node (ref "U3") (pin "26") (pinfunction "PB13_26") (pintype "passive"))
    )
    (net (code "41") (name "/PB14") (class "Default")
      (node (ref "R42") (pin "2") (pinfunction "2_2") (pintype "passive"))
      (node (ref "U3") (pin "27") (pinfunction "PB14_27") (pintype "passive"))
    )
    (net (code "42") (name "/PB15") (class "Default")
      (node (ref "U3") (pin "28") (pinfunction "PB15_28") (pintype "passive"))
    )
    (net (code "43") (name "/PC13") (class "Default")
      (node (ref "R39") (pin "2") (pinfunction "2_2") (pintype "passive"))
      (node (ref "U3") (pin "2") (pinfunction "PC13-TAMPER-RTC_2") (pintype "passive"))
    )
    (net (code "44") (name "/PC14") (class "Default")
      (node (ref "R40") (pin "2") (pinfunction "2_2") (pintype "passive"))
      (node (ref "U3") (pin "3") (pinfunction "PC14-OSC32_IN_3") (pintype "passive"))
    )
    (net (code "45") (name "/PC15") (class "Default")
      (node (ref "R41") (pin "2") (pinfunction "2_2") (pintype "passive"))
      (node (ref "U3") (pin "4") (pinfunction "PC15-OSC32_OUT_4") (pintype "passive"))
    )
    (net (code "46") (name "/RESET") (class "Default")
      (node (ref "C14") (pin "1") (pinfunction "1_1") (pintype "passive"))
      (node (ref "R32") (pin "1") (pinfunction "1_1") (pintype "passive"))
      (node (ref "U3") (pin "7") (pinfunction "NRST_7") (pintype "passive"))
    )
    (net (code "47") (name "/SCL") (class "Default")
      (node (ref "R38") (pin "2") (pinfunction "2_2") (pintype "passive"))
      (node (ref "U3") (pin "35") (pinfunction "PF6_35") (pintype "passive"))
    )
    (net (code "48") (name "/SDA") (class "Default")
      (node (ref "R45") (pin "2") (pinfunction "2_2") (pintype "passive"))
      (node (ref "U3") (pin "36") (pinfunction "PF7_36") (pintype "passive"))
    )
    (net (code "49") (name "/SWCLK") (class "Default")
      (node (ref "P11") (pin "4") (pinfunction "4_4") (pintype "passive"))
      (node (ref "U3") (pin "37") (pinfunction "PA14_37") (pintype "passive"))
    )
    (net (code "50") (name "/SWDIO") (class "Default")
      (node (ref "P11") (pin "3") (pinfunction "3_3") (pintype "passive"))
      (node (ref "U3") (pin "34") (pinfunction "SWIO_34") (pintype "passive"))
    )
    (net (code "51") (name "/Speed") (class "Default")
      (node (ref "JP14") (pin "2") (pinfunction "2_2") (pintype "passive"))
      (node (ref "JP15") (pin "2") (pinfunction "2_2") (pintype "passive"))
      (node (ref "JP17") (pin "2") (pinfunction "2_2") (pintype "passive"))
      (node (ref "JP18") (pin "2") (pinfunction "2_2") (pintype "passive"))
      (node (ref "JP19") (pin "2") (pinfunction "2_2") (pintype "passive"))
      (node (ref "JP20") (pin "2") (pinfunction "2_2") (pintype "passive"))
      (node (ref "JP21") (pin "2") (pinfunction "2_2") (pintype "passive"))
      (node (ref "R109") (pin "2") (pinfunction "2_2") (pintype "passive"))
      (node (ref "Y14") (pin "3") (pinfunction "C_3") (pintype "passive"))
      (node (ref "Y15") (pin "3") (pinfunction "C_3") (pintype "passive"))
      (node (ref "Y19") (pin "3") (pinfunction "C_3") (pintype "passive"))
      (node (ref "Y20") (pin "3") (pinfunction "C_3") (pintype "passive"))
      (node (ref "Y22") (pin "3") (pinfunction "C_3") (pintype "passive"))
      (node (ref "Y23") (pin "3") (pinfunction "C_3") (pintype "passive"))
      (node (ref "Y31") (pin "3") (pinfunction "C_3") (pintype "passive"))
    )
    (net (code "52") (name "/TH1") (class "Default")
      (node (ref "P11") (pin "5") (pinfunction "5_5") (pintype "passive"))
      (node (ref "U3") (pin "43") (pinfunction "PB7_43") (pintype "passive"))
    )
    (net (code "53") (name "/mode1") (class "Default")
      (node (ref "R22") (pin "2") (pinfunction "2_2") (pintype "passive"))
      (node (ref "U3") (pin "39") (pinfunction "PB3_39") (pintype "passive"))
    )
    (net (code "59") (name "3.3V") (class "Default")
      (node (ref "C2") (pin "1") (pinfunction "1_1") (pintype "passive"))
      (node (ref "C25") (pin "1") (pinfunction "1_1") (pintype "passive"))
      (node (ref "C3") (pin "1") (pinfunction "1_1") (pintype "passive"))
      (node (ref "C6") (pin "2") (pinfunction "2_2") (pintype "passive"))
      (node (ref "C7") (pin "2") (pinfunction "2_2") (pintype "passive"))
      (node (ref "C8") (pin "2") (pinfunction "2_2") (pintype "passive"))
      (node (ref "C9") (pin "2") (pinfunction "2_2") (pintype "passive"))
      (node (ref "P11") (pin "1") (pinfunction "1_1") (pintype "passive"))
      (node (ref "R32") (pin "2") (pinfunction "2_2") (pintype "passive"))
      (node (ref "R33") (pin "2") (pinfunction "2_2") (pintype "passive"))
      (node (ref "R34") (pin "2") (pinfunction "2_2") (pintype "passive"))
      (node (ref "R66") (pin "1") (pinfunction "1_1") (pintype "passive"))
      (node (ref "R9") (pin "1") (pinfunction "1_1") (pintype "passive"))
      (node (ref "U2") (pin "2") (pinfunction "OUT_2") (pintype "passive"))
      (node (ref "U2") (pin "4") (pinfunction "OUT_4") (pintype "passive"))
      (node (ref "U3") (pin "1") (pinfunction "VBAT_1") (pintype "passive"))
      (node (ref "U3") (pin "24") (pinfunction "VDD_1_24") (pintype "passive"))
      (node (ref "U3") (pin "48") (pinfunction "VDD_3_48") (pintype "passive"))
    )
    (net (code "60") (name "5.5V") (class "Default")
      (node (ref "P20") (pin "2") (pinfunction "2_2") (pintype "passive"))
      (node (ref "P24") (pin "2") (pinfunction "2_2") (pintype "passive"))
      (node (ref "R71") (pin "1") (pinfunction "1_1") (pintype "passive"))
    )
    (net (code "61") (name "5V") (class "Default")
      (node (ref "R1") (pin "1") (pinfunction "1_1") (pintype "passive"))
      (node (ref "R11") (pin "1") (pinfunction "1_1") (pintype "passive"))
      (node (ref "R12") (pin "1") (pinfunction "1_1") (pintype "passive"))
      (node (ref "R13") (pin "1") (pinfunction "1_1") (pintype "passive"))
      (node (ref "R14") (pin "1") (pinfunction "1_1") (pintype "passive"))
      (node (ref "R15") (pin "1") (pinfunction "1_1") (pintype "passive"))
      (node (ref "R16") (pin "1") (pinfunction "1_1") (pintype "passive"))
      (node (ref "R17") (pin "1") (pinfunction "1_1") (pintype "passive"))
      (node (ref "R2") (pin "1") (pinfunction "1_1") (pintype "passive"))
      (node (ref "R29") (pin "1") (pinfunction "1_1") (pintype "passive"))
      (node (ref "R3") (pin "1") (pinfunction "1_1") (pintype "passive"))
      (node (ref "R30") (pin "1") (pinfunction "1_1") (pintype "passive"))
      (node (ref "R31") (pin "1") (pinfunction "1_1") (pintype "passive"))
      (node (ref "R65") (pin "2") (pinfunction "2_2") (pintype "passive"))
      (node (ref "R66") (pin "2") (pinfunction "2_2") (pintype "passive"))
    )
    (net (code "62") (name "5V+") (class "Default")
      (node (ref "C16") (pin "1") (pinfunction "1_1") (pintype "passive"))
      (node (ref "C17") (pin "1") (pinfunction "1_1") (pintype "passive"))
      (node (ref "C5") (pin "1") (pinfunction "1_1") (pintype "passive"))
      (node (ref "D2") (pin "2") (pinfunction "K_2") (pintype "passive"))
      (node (ref "R65") (pin "1") (pinfunction "1_1") (pintype "passive"))
      (node (ref "U1") (pin "3") (pinfunction "OUT_3") (pintype "passive"))
      (node (ref "U2") (pin "3") (pinfunction "IN_3") (pintype "passive"))
    )
    (net (code "63") (name "5V2") (class "Default")
      (node (ref "P19") (pin "2") (pinfunction "2_2") (pintype "passive"))
      (node (ref "P24") (pin "1") (pinfunction "1_1") (pintype "passive"))
      (node (ref "R69") (pin "1") (pinfunction "1_1") (pintype "passive"))
    )
    (net (code "64") (name "12V") (class "Default")
      (node (ref "C24") (pin "1") (pinfunction "1_1") (pintype "passive"))
      (node (ref "C4") (pin "1") (pinfunction "1_1") (pintype "passive"))
      (node (ref "D1") (pin "2") (pinfunction "K_2") (pintype "passive"))
      (node (ref "JP11") (pin "1") (pinfunction "1_1") (pintype "passive"))
      (node (ref "JP12") (pin "1") (pinfunction "1_1") (pintype "passive"))
      (node (ref "JP13") (pin "1") (pinfunction "1_1") (pintype "passive"))
      (node (ref "P2") (pin "2") (pinfunction "2_2") (pintype "passive"))
      (node (ref "R120") (pin "2") (pinfunction "2_2") (pintype "passive"))
      (node (ref "R121") (pin "2") (pinfunction "2_2") (pintype "passive"))
      (node (ref "R26") (pin "1") (pinfunction "1_1") (pintype "passive"))
      (node (ref "U1") (pin "1") (pinfunction "IN_1") (pintype "passive"))
      (node (ref "Y28") (pin "2") (pinfunction "E_2") (pintype "passive"))
      (node (ref "Y29") (pin "2") (pinfunction "E_2") (pintype "passive"))
      (node (ref "Y30") (pin "2") (pinfunction "E_2") (pintype "passive"))
    )
    (net (code "65") (name "40V") (class "Default")
      (node (ref "C18") (pin "1") (pinfunction "1_1") (pintype "passive"))
      (node (ref "JP15") (pin "1") (pinfunction "1_1") (pintype "passive"))
      (node (ref "R57") (pin "1") (pinfunction "1_1") (pintype "passive"))
      (node (ref "R59") (pin "2") (pinfunction "2_2") (pintype "passive"))
      (node (ref "R72") (pin "2") (pinfunction "2_2") (pintype "passive"))
      (node (ref "Y15") (pin "2") (pinfunction "E_2") (pintype "passive"))
    )
    (net (code "66") (name "48V") (class "Default")
      (node (ref "C23") (pin "1") (pinfunction "1_1") (pintype "passive"))
      (node (ref "JP20") (pin "1") (pinfunction "1_1") (pintype "passive"))
      (node (ref "R102") (pin "2") (pinfunction "2_2") (pintype "passive"))
      (node (ref "R55") (pin "1") (pinfunction "1_1") (pintype "passive"))
      (node (ref "R68") (pin "2") (pinfunction "2_2") (pintype "passive"))
      (node (ref "Y23") (pin "2") (pinfunction "E_2") (pintype "passive"))
    )
    (net (code "67") (name "55V") (class "Default")
      (node (ref "C15") (pin "1") (pinfunction "1_1") (pintype "passive"))
      (node (ref "JP14") (pin "1") (pinfunction "1_1") (pintype "passive"))
      (node (ref "R56") (pin "1") (pinfunction "1_1") (pintype "passive"))
      (node (ref "R58") (pin "2") (pinfunction "2_2") (pintype "passive"))
      (node (ref "R70") (pin "2") (pinfunction "2_2") (pintype "passive"))
      (node (ref "Y14") (pin "2") (pinfunction "E_2") (pintype "passive"))
    )
    (net (code "68") (name "65V") (class "Default")
      (node (ref "C21") (pin "1") (pinfunction "1_1") (pintype "passive"))
      (node (ref "JP18") (pin "1") (pinfunction "1_1") (pintype "passive"))
      (node (ref "R100") (pin "2") (pinfunction "2_2") (pintype "passive"))
      (node (ref "R53") (pin "1") (pinfunction "1_1") (pintype "passive"))
      (node (ref "R61") (pin "2") (pinfunction "2_2") (pintype "passive"))
      (node (ref "Y20") (pin "2") (pinfunction "E_2") (pintype "passive"))
    )
    (net (code "69") (name "72V") (class "Default")
      (node (ref "C22") (pin "1") (pinfunction "1_1") (pintype "passive"))
      (node (ref "JP19") (pin "1") (pinfunction "1_1") (pintype "passive"))
      (node (ref "R101") (pin "2") (pinfunction "2_2") (pintype "passive"))
      (node (ref "R54") (pin "1") (pinfunction "1_1") (pintype "passive"))
      (node (ref "R63") (pin "2") (pinfunction "2_2") (pintype "passive"))
      (node (ref "Y22") (pin "2") (pinfunction "E_2") (pintype "passive"))
    )
    (net (code "70") (name "80V") (class "Default")
      (node (ref "C20") (pin "1") (pinfunction "1_1") (pintype "passive"))
      (node (ref "JP17") (pin "1") (pinfunction "1_1") (pintype "passive"))
      (node (ref "R52") (pin "1") (pinfunction "1_1") (pintype "passive"))
      (node (ref "R60") (pin "2") (pinfunction "2_2") (pintype "passive"))
      (node (ref "R99") (pin "2") (pinfunction "2_2") (pintype "passive"))
      (node (ref "Y19") (pin "2") (pinfunction "E_2") (pintype "passive"))
    )
    (net (code "71") (name "100V") (class "Default")
      (node (ref "C1") (pin "1") (pinfunction "1_1") (pintype "passive"))
      (node (ref "C19") (pin "1") (pinfunction "1_1") (pintype "passive"))
      (node (ref "JP16") (pin "1") (pinfunction "1_1") (pintype "passive"))
      (node (ref "JP21") (pin "1") (pinfunction "1_1") (pintype "passive"))
      (node (ref "P1") (pin "2") (pinfunction "2_2") (pintype "passive"))
      (node (ref "P3") (pin "2") (pinfunction "2_2") (pintype "passive"))
      (node (ref "R27") (pin "2") (pinfunction "2_2") (pintype "passive"))
      (node (ref "R52") (pin "2") (pinfunction "2_2") (pintype "passive"))
      (node (ref "R53") (pin "2") (pinfunction "2_2") (pintype "passive"))
      (node (ref "R54") (pin "2") (pinfunction "2_2") (pintype "passive"))
      (node (ref "R55") (pin "2") (pinfunction "2_2") (pintype "passive"))
      (node (ref "R56") (pin "2") (pinfunction "2_2") (pintype "passive"))
      (node (ref "R57") (pin "2") (pinfunction "2_2") (pintype "passive"))
      (node (ref "R97") (pin "2") (pinfunction "2_2") (pintype "passive"))
      (node (ref "Y18") (pin "2") (pinfunction "E_2") (pintype "passive"))
      (node (ref "Y31") (pin "2") (pinfunction "E_2") (pintype "passive"))
    )
    (net (code "72") (name "GND") (class "Default")
      (node (ref "C1") (pin "2") (pinfunction "2_2") (pintype "passive"))
      (node (ref "C10") (pin "1") (pinfunction "1_1") (pintype "passive"))
      (node (ref "C11") (pin "1") (pinfunction "1_1") (pintype "passive"))
      (node (ref "C12") (pin "1") (pinfunction "1_1") (pintype "passive"))
      (node (ref "C13") (pin "1") (pinfunction "1_1") (pintype "passive"))
      (node (ref "C14") (pin "2") (pinfunction "2_2") (pintype "passive"))
      (node (ref "C15") (pin "2") (pinfunction "2_2") (pintype "passive"))
      (node (ref "C16") (pin "2") (pinfunction "2_2") (pintype "passive"))
      (node (ref "C17") (pin "2") (pinfunction "2_2") (pintype "passive"))
      (node (ref "C18") (pin "2") (pinfunction "2_2") (pintype "passive"))
      (node (ref "C19") (pin "2") (pinfunction "2_2") (pintype "passive"))
      (node (ref "C2") (pin "2") (pinfunction "2_2") (pintype "passive"))
      (node (ref "C20") (pin "2") (pinfunction "2_2") (pintype "passive"))
      (node (ref "C21") (pin "2") (pinfunction "2_2") (pintype "passive"))
      (node (ref "C22") (pin "2") (pinfunction "2_2") (pintype "passive"))
      (node (ref "C23") (pin "2") (pinfunction "2_2") (pintype "passive"))
      (node (ref "C24") (pin "2") (pinfunction "2_2") (pintype "passive"))
      (node (ref "C25") (pin "2") (pinfunction "2_2") (pintype "passive"))
      (node (ref "C26") (pin "1") (pinfunction "1_1") (pintype "passive"))
      (node (ref "C27") (pin "1") (pinfunction "1_1") (pintype "passive"))
      (node (ref "C28") (pin "1") (pinfunction "1_1") (pintype "passive"))
      (node (ref "C29") (pin "1") (pinfunction "1_1") (pintype "passive"))
      (node (ref "C3") (pin "2") (pinfunction "2_2") (pintype "passive"))
      (node (ref "C30") (pin "1") (pinfunction "1_1") (pintype "passive"))
      (node (ref "C31") (pin "1") (pinfunction "1_1") (pintype "passive"))
      (node (ref "C32") (pin "1") (pinfunction "1_1") (pintype "passive"))
      (node (ref "C33") (pin "1") (pinfunction "1_1") (pintype "passive"))
      (node (ref "C34") (pin "1") (pinfunction "1_1") (pintype "passive"))
      (node (ref "C35") (pin "1") (pinfunction "1_1") (pintype "passive"))
      (node (ref "C36") (pin "1") (pinfunction "1_1") (pintype "passive"))
      (node (ref "C37") (pin "1") (pinfunction "1_1") (pintype "passive"))
      (node (ref "C38") (pin "1") (pinfunction "1_1") (pintype "passive"))
      (node (ref "C39") (pin "1") (pinfunction "1_1") (pintype "passive"))
      (node (ref "C4") (pin "2") (pinfunction "2_2") (pintype "passive"))
      (node (ref "C40") (pin "1") (pinfunction "1_1") (pintype "passive"))
      (node (ref "C5") (pin "2") (pinfunction "2_2") (pintype "passive"))
      (node (ref "C6") (pin "1") (pinfunction "1_1") (pintype "passive"))
      (node (ref "C7") (pin "1") (pinfunction "1_1") (pintype "passive"))
      (node (ref "C8") (pin "1") (pinfunction "1_1") (pintype "passive"))
      (node (ref "C9") (pin "1") (pinfunction "1_1") (pintype "passive"))
      (node (ref "D1") (pin "1") (pinfunction "A_1") (pintype "passive"))
      (node (ref "D2") (pin "1") (pinfunction "A_1") (pintype "passive"))
      (node (ref "D6") (pin "2") (pinfunction "K_2") (pintype "passive"))
      (node (ref "D7") (pin "2") (pinfunction "K_2") (pintype "passive"))
      (node (ref "D8") (pin "2") (pinfunction "K_2") (pintype "passive"))
      (node (ref "JP1") (pin "2") (pinfunction "2_2") (pintype "passive"))
      (node (ref "JP10") (pin "2") (pinfunction "2_2") (pintype "passive"))
      (node (ref "JP2") (pin "2") (pinfunction "2_2") (pintype "passive"))
      (node (ref "JP3") (pin "2") (pinfunction "2_2") (pintype "passive"))
      (node (ref "JP4") (pin "2") (pinfunction "2_2") (pintype "passive"))
      (node (ref "JP5") (pin "2") (pinfunction "2_2") (pintype "passive"))
      (node (ref "JP6") (pin "2") (pinfunction "2_2") (pintype "passive"))
      (node (ref "JP7") (pin "2") (pinfunction "2_2") (pintype "passive"))
      (node (ref "JP8") (pin "2") (pinfunction "2_2") (pintype "passive"))
      (node (ref "JP9") (pin "2") (pinfunction "2_2") (pintype "passive"))
      (node (ref "P1") (pin "1") (pinfunction "1_1") (pintype "passive"))
      (node (ref "P11") (pin "2") (pinfunction "2_2") (pintype "passive"))
      (node (ref "P19") (pin "1") (pinfunction "1_1") (pintype "passive"))
      (node (ref "P2") (pin "1") (pinfunction "1_1") (pintype "passive"))
      (node (ref "P20") (pin "1") (pinfunction "1_1") (pintype "passive"))
      (node (ref "P22") (pin "1") (pinfunction "1_1") (pintype "passive"))
      (node (ref "P24") (pin "5") (pinfunction "5_5") (pintype "passive"))
      (node (ref "P3") (pin "1") (pinfunction "1_1") (pintype "passive"))
      (node (ref "R10") (pin "1") (pinfunction "1_1") (pintype "passive"))
      (node (ref "R108") (pin "1") (pinfunction "1_1") (pintype "passive"))
      (node (ref "R114") (pin "1") (pinfunction "1_1") (pintype "passive"))
      (node (ref "R115") (pin "1") (pinfunction "1_1") (pintype "passive"))
      (node (ref "R116") (pin "1") (pinfunction "1_1") (pintype "passive"))
      (node (ref "R117") (pin "1") (pinfunction "1_1") (pintype "passive"))
      (node (ref "R118") (pin "1") (pinfunction "1_1") (pintype "passive"))
      (node (ref "R19") (pin "1") (pinfunction "1_1") (pintype "passive"))
      (node (ref "R23") (pin "1") (pinfunction "1_1") (pintype "passive"))
      (node (ref "R24") (pin "1") (pinfunction "1_1") (pintype "passive"))
      (node (ref "R25") (pin "1") (pinfunction "1_1") (pintype "passive"))
      (node (ref "R47") (pin "1") (pinfunction "1_1") (pintype "passive"))
      (node (ref "R48") (pin "1") (pinfunction "1_1") (pintype "passive"))
      (node (ref "R49") (pin "1") (pinfunction "1_1") (pintype "passive"))
      (node (ref "R50") (pin "1") (pinfunction "1_1") (pintype "passive"))
      (node (ref "R51") (pin "1") (pinfunction "1_1") (pintype "passive"))
      (node (ref "R64") (pin "1") (pinfunction "1_1") (pintype "passive"))
      (node (ref "R67") (pin "1") (pinfunction "1_1") (pintype "passive"))
      (node (ref "R7") (pin "1") (pinfunction "1_1") (pintype "passive"))
      (node (ref "R78") (pin "1") (pinfunction "1_1") (pintype "passive"))
      (node (ref "R79") (pin "1") (pinfunction "1_1") (pintype "passive"))
      (node (ref "R8") (pin "1") (pinfunction "1_1") (pintype "passive"))
      (node (ref "R81") (pin "1") (pinfunction "1_1") (pintype "passive"))
      (node (ref "R83") (pin "1") (pinfunction "1_1") (pintype "passive"))
      (node (ref "R85") (pin "1") (pinfunction "1_1") (pintype "passive"))
      (node (ref "R88") (pin "1") (pinfunction "1_1") (pintype "passive"))
      (node (ref "R90") (pin "1") (pinfunction "1_1") (pintype "passive"))
      (node (ref "R91") (pin "1") (pinfunction "1_1") (pintype "passive"))
      (node (ref "R92") (pin "2") (pinfunction "2_2") (pintype "passive"))
      (node (ref "R93") (pin "2") (pinfunction "2_2") (pintype "passive"))
      (node (ref "U1") (pin "2") (pinfunction "GND_2") (pintype "passive"))
      (node (ref "U2") (pin "1") (pinfunction "GND_1") (pintype "passive"))
      (node (ref "U3") (pin "23") (pinfunction "VSS_1_23") (pintype "passive"))
      (node (ref "U3") (pin "47") (pinfunction "VSS_3_47") (pintype "passive"))
      (node (ref "U3") (pin "8") (pinfunction "VSSA_8") (pintype "passive"))
      (node (ref "Y1") (pin "2") (pinfunction "E_2") (pintype "passive"))
      (node (ref "Y11") (pin "2") (pinfunction "E_2") (pintype "passive"))
      (node (ref "Y12") (pin "2") (pinfunction "E_2") (pintype "passive"))
      (node (ref "Y13") (pin "2") (pinfunction "E_2") (pintype "passive"))
      (node (ref "Y2") (pin "2") (pinfunction "E_2") (pintype "passive"))
      (node (ref "Y3") (pin "2") (pinfunction "E_2") (pintype "passive"))
      (node (ref "Y4") (pin "2") (pinfunction "E_2") (pintype "passive"))
      (node (ref "Y5") (pin "2") (pinfunction "E_2") (pintype "passive"))
      (node (ref "Y6") (pin "2") (pinfunction "E_2") (pintype "passive"))
      (node (ref "Y7") (pin "2") (pinfunction "E_2") (pintype "passive"))
    )
    (net (code "73") (name "Net-(D3-Pad1)") (class "Default")
      (node (ref "D3") (pin "1") (pinfunction "1_1") (pintype "passive"))
      (node (ref "R14") (pin "2") (pinfunction "2_2") (pintype "passive"))
    )
    (net (code "74") (name "Net-(D4-Pad1)") (class "Default")
      (node (ref "D4") (pin "1") (pinfunction "1_1") (pintype "passive"))
      (node (ref "R11") (pin "2") (pinfunction "2_2") (pintype "passive"))
    )
    (net (code "75") (name "Net-(D5-Pad1)") (class "Default")
      (node (ref "D5") (pin "1") (pinfunction "1_1") (pintype "passive"))
      (node (ref "R12") (pin "2") (pinfunction "2_2") (pintype "passive"))
    )
    (net (code "76") (name "Net-(D6-A)") (class "Default")
      (node (ref "D6") (pin "1") (pinfunction "A_1") (pintype "passive"))
      (node (ref "R35") (pin "1") (pinfunction "1_1") (pintype "passive"))
    )
    (net (code "77") (name "Net-(D7-A)") (class "Default")
      (node (ref "D7") (pin "1") (pinfunction "A_1") (pintype "passive"))
      (node (ref "R36") (pin "1") (pinfunction "1_1") (pintype "passive"))
    )
    (net (code "78") (name "Net-(D8-A)") (class "Default")
      (node (ref "D8") (pin "1") (pinfunction "A_1") (pintype "passive"))
      (node (ref "R37") (pin "1") (pinfunction "1_1") (pintype "passive"))
    )
    (net (code "79") (name "Net-(P18-Pad1)") (class "Default")
      (node (ref "P18") (pin "1") (pinfunction "1_1") (pintype "passive"))
      (node (ref "R33") (pin "1") (pinfunction "1_1") (pintype "passive"))
      (node (ref "R38") (pin "1") (pinfunction "1_1") (pintype "passive"))
    )
    (net (code "80") (name "Net-(P18-Pad2)") (class "Default")
      (node (ref "P18") (pin "2") (pinfunction "2_2") (pintype "passive"))
      (node (ref "R34") (pin "1") (pinfunction "1_1") (pintype "passive"))
      (node (ref "R45") (pin "1") (pinfunction "1_1") (pintype "passive"))
    )
    (net (code "81") (name "Net-(R27-Pad1)") (class "Default")
      (node (ref "R27") (pin "1") (pinfunction "1_1") (pintype "passive"))
      (node (ref "R28") (pin "2") (pinfunction "2_2") (pintype "passive"))
      (node (ref "R82") (pin "1") (pinfunction "1_1") (pintype "passive"))
    )
    (net (code "82") (name "Net-(R46-Pad1)") (class "Default")
      (node (ref "R46") (pin "1") (pinfunction "1_1") (pintype "passive"))
      (node (ref "R97") (pin "1") (pinfunction "1_1") (pintype "passive"))
      (node (ref "R98") (pin "2") (pinfunction "2_2") (pintype "passive"))
    )
    (net (code "83") (name "Net-(R58-Pad1)") (class "Default")
      (node (ref "R58") (pin "1") (pinfunction "1_1") (pintype "passive"))
      (node (ref "R74") (pin "2") (pinfunction "2_2") (pintype "passive"))
      (node (ref "R80") (pin "1") (pinfunction "1_1") (pintype "passive"))
    )
    (net (code "84") (name "Net-(R59-Pad1)") (class "Default")
      (node (ref "R59") (pin "1") (pinfunction "1_1") (pintype "passive"))
      (node (ref "R73") (pin "1") (pinfunction "1_1") (pintype "passive"))
      (node (ref "R75") (pin "2") (pinfunction "2_2") (pintype "passive"))
    )
    (net (code "85") (name "Net-(R60-Pad1)") (class "Default")
      (node (ref "R60") (pin "1") (pinfunction "1_1") (pintype "passive"))
      (node (ref "R78") (pin "2") (pinfunction "2_2") (pintype "passive"))
    )
    (net (code "86") (name "Net-(R61-Pad1)") (class "Default")
      (node (ref "R61") (pin "1") (pinfunction "1_1") (pintype "passive"))
      (node (ref "R79") (pin "2") (pinfunction "2_2") (pintype "passive"))
    )
    (net (code "87") (name "Net-(R63-Pad1)") (class "Default")
      (node (ref "R63") (pin "1") (pinfunction "1_1") (pintype "passive"))
      (node (ref "R81") (pin "2") (pinfunction "2_2") (pintype "passive"))
    )
    (net (code "88") (name "Net-(R68-Pad1)") (class "Default")
      (node (ref "R68") (pin "1") (pinfunction "1_1") (pintype "passive"))
      (node (ref "R83") (pin "2") (pinfunction "2_2") (pintype "passive"))
    )
    (net (code "89") (name "Net-(R70-Pad1)") (class "Default")
      (node (ref "R70") (pin "1") (pinfunction "1_1") (pintype "passive"))
      (node (ref "R85") (pin "2") (pinfunction "2_2") (pintype "passive"))
    )
    (net (code "90") (name "Net-(R72-Pad1)") (class "Default")
      (node (ref "R72") (pin "1") (pinfunction "1_1") (pintype "passive"))
      (node (ref "R88") (pin "2") (pinfunction "2_2") (pintype "passive"))
    )
    (net (code "91") (name "Net-(R100-Pad1)") (class "Default")
      (node (ref "R100") (pin "1") (pinfunction "1_1") (pintype "passive"))
      (node (ref "R104") (pin "2") (pinfunction "2_2") (pintype "passive"))
      (node (ref "R87") (pin "1") (pinfunction "1_1") (pintype "passive"))
    )
    (net (code "92") (name "Net-(R101-Pad1)") (class "Default")
      (node (ref "R101") (pin "1") (pinfunction "1_1") (pintype "passive"))
      (node (ref "R106") (pin "2") (pinfunction "2_2") (pintype "passive"))
      (node (ref "R89") (pin "1") (pinfunction "1_1") (pintype "passive"))
    )
    (net (code "93") (name "Net-(R102-Pad1)") (class "Default")
      (node (ref "R102") (pin "1") (pinfunction "1_1") (pintype "passive"))
      (node (ref "R107") (pin "2") (pinfunction "2_2") (pintype "passive"))
      (node (ref "R84") (pin "1") (pinfunction "1_1") (pintype "passive"))
    )
    (net (code "94") (name "Net-(R103-Pad2)") (class "Default")
      (node (ref "R103") (pin "2") (pinfunction "2_2") (pintype "passive"))
      (node (ref "R86") (pin "1") (pinfunction "1_1") (pintype "passive"))
      (node (ref "R99") (pin "1") (pinfunction "1_1") (pintype "passive"))
    )
    (net (code "95") (name "Net-(U3-PD0-OSC_IN)") (class "Default")
      (node (ref "C10") (pin "2") (pinfunction "2_2") (pintype "passive"))
      (node (ref "U3") (pin "5") (pinfunction "PD0-OSC_IN_5") (pintype "passive"))
      (node (ref "Y0") (pin "2") (pinfunction "2_2") (pintype "passive"))
    )
    (net (code "96") (name "Net-(U3-PD1-OSC_OUT)") (class "Default")
      (node (ref "C11") (pin "2") (pinfunction "2_2") (pintype "passive"))
      (node (ref "U3") (pin "6") (pinfunction "PD1-OSC_OUT_6") (pintype "passive"))
      (node (ref "Y0") (pin "1") (pinfunction "1_1") (pintype "passive"))
    )
    (net (code "97") (name "Net-(U3-VDDA)") (class "Default")
      (node (ref "C12") (pin "2") (pinfunction "2_2") (pintype "passive"))
      (node (ref "C13") (pin "2") (pinfunction "2_2") (pintype "passive"))
      (node (ref "R9") (pin "2") (pinfunction "2_2") (pintype "passive"))
      (node (ref "U3") (pin "9") (pinfunction "VDDA_9") (pintype "passive"))
    )
    (net (code "98") (name "Net-(Y1-B)") (class "Default")
      (node (ref "R4") (pin "1") (pinfunction "1_1") (pintype "passive"))
      (node (ref "R7") (pin "2") (pinfunction "2_2") (pintype "passive"))
      (node (ref "Y1") (pin "1") (pinfunction "B_1") (pintype "passive"))
    )
    (net (code "99") (name "Net-(Y2-B)") (class "Default")
      (node (ref "R5") (pin "1") (pinfunction "1_1") (pintype "passive"))
      (node (ref "R8") (pin "2") (pinfunction "2_2") (pintype "passive"))
      (node (ref "Y2") (pin "1") (pinfunction "B_1") (pintype "passive"))
    )
    (net (code "100") (name "Net-(Y3-B)") (class "Default")
      (node (ref "R10") (pin "2") (pinfunction "2_2") (pintype "passive"))
      (node (ref "R6") (pin "1") (pinfunction "1_1") (pintype "passive"))
      (node (ref "Y3") (pin "1") (pinfunction "B_1") (pintype "passive"))
    )
    (net (code "101") (name "Net-(Y4-B)") (class "Default")
      (node (ref "R18") (pin "1") (pinfunction "1_1") (pintype "passive"))
      (node (ref "R19") (pin "2") (pinfunction "2_2") (pintype "passive"))
      (node (ref "Y4") (pin "1") (pinfunction "B_1") (pintype "passive"))
    )
    (net (code "102") (name "Net-(Y5-B)") (class "Default")
      (node (ref "R20") (pin "1") (pinfunction "1_1") (pintype "passive"))
      (node (ref "R23") (pin "2") (pinfunction "2_2") (pintype "passive"))
      (node (ref "Y5") (pin "1") (pinfunction "B_1") (pintype "passive"))
    )
    (net (code "103") (name "Net-(Y6-B)") (class "Default")
      (node (ref "R21") (pin "1") (pinfunction "1_1") (pintype "passive"))
      (node (ref "R24") (pin "2") (pinfunction "2_2") (pintype "passive"))
      (node (ref "Y6") (pin "1") (pinfunction "B_1") (pintype "passive"))
    )
    (net (code "104") (name "Net-(Y7-B)") (class "Default")
      (node (ref "R22") (pin "1") (pinfunction "1_1") (pintype "passive"))
      (node (ref "R25") (pin "2") (pinfunction "2_2") (pintype "passive"))
      (node (ref "Y7") (pin "1") (pinfunction "B_1") (pintype "passive"))
    )
    (net (code "105") (name "Net-(Y8-B)") (class "Default")
      (node (ref "R39") (pin "1") (pinfunction "1_1") (pintype "passive"))
      (node (ref "Y8") (pin "1") (pinfunction "B_1") (pintype "passive"))
    )
    (net (code "106") (name "Net-(Y8-E)") (class "Default")
      (node (ref "R47") (pin "2") (pinfunction "2_2") (pintype "passive"))
      (node (ref "Y8") (pin "2") (pinfunction "E_2") (pintype "passive"))
    )
    (net (code "107") (name "Net-(Y9-B)") (class "Default")
      (node (ref "R40") (pin "1") (pinfunction "1_1") (pintype "passive"))
      (node (ref "Y9") (pin "1") (pinfunction "B_1") (pintype "passive"))
    )
    (net (code "108") (name "Net-(Y9-E)") (class "Default")
      (node (ref "R48") (pin "2") (pinfunction "2_2") (pintype "passive"))
      (node (ref "Y9") (pin "2") (pinfunction "E_2") (pintype "passive"))
    )
    (net (code "109") (name "Net-(Y10-B)") (class "Default")
      (node (ref "R41") (pin "1") (pinfunction "1_1") (pintype "passive"))
      (node (ref "Y10") (pin "1") (pinfunction "B_1") (pintype "passive"))
    )
    (net (code "110") (name "Net-(Y10-C)") (class "Default")
      (node (ref "R121") (pin "1") (pinfunction "1_1") (pintype "passive"))
      (node (ref "Y10") (pin "3") (pinfunction "C_3") (pintype "passive"))
      (node (ref "Y30") (pin "1") (pinfunction "B_1") (pintype "passive"))
    )
    (net (code "111") (name "Net-(Y10-E)") (class "Default")
      (node (ref "R67") (pin "2") (pinfunction "2_2") (pintype "passive"))
      (node (ref "Y10") (pin "2") (pinfunction "E_2") (pintype "passive"))
    )
    (net (code "112") (name "Net-(Y11-B)") (class "Default")
      (node (ref "R42") (pin "1") (pinfunction "1_1") (pintype "passive"))
      (node (ref "R49") (pin "2") (pinfunction "2_2") (pintype "passive"))
      (node (ref "Y11") (pin "1") (pinfunction "B_1") (pintype "passive"))
    )
    (net (code "113") (name "Net-(Y12-B)") (class "Default")
      (node (ref "R43") (pin "1") (pinfunction "1_1") (pintype "passive"))
      (node (ref "R50") (pin "2") (pinfunction "2_2") (pintype "passive"))
      (node (ref "Y12") (pin "1") (pinfunction "B_1") (pintype "passive"))
    )
    (net (code "114") (name "Net-(Y13-B)") (class "Default")
      (node (ref "R44") (pin "1") (pinfunction "1_1") (pintype "passive"))
      (node (ref "R51") (pin "2") (pinfunction "2_2") (pintype "passive"))
      (node (ref "Y13") (pin "1") (pinfunction "B_1") (pintype "passive"))
    )
    (net (code "115") (name "Net-(Y14-B)") (class "Default")
      (node (ref "R74") (pin "1") (pinfunction "1_1") (pintype "passive"))
      (node (ref "Y14") (pin "1") (pinfunction "B_1") (pintype "passive"))
    )
    (net (code "116") (name "Net-(Y15-B)") (class "Default")
      (node (ref "R75") (pin "1") (pinfunction "1_1") (pintype "passive"))
      (node (ref "Y15") (pin "1") (pinfunction "B_1") (pintype "passive"))
    )
    (net (code "117") (name "Net-(Y16-B)") (class "Default")
      (node (ref "R76") (pin "2") (pinfunction "2_2") (pintype "passive"))
      (node (ref "Y16") (pin "1") (pinfunction "B_1") (pintype "passive"))
    )
    (net (code "118") (name "Net-(Y16-C)") (class "Default")
      (node (ref "R80") (pin "2") (pinfunction "2_2") (pintype "passive"))
      (node (ref "Y16") (pin "3") (pinfunction "C_3") (pintype "passive"))
    )
    (net (code "119") (name "Net-(Y16-E)") (class "Default")
      (node (ref "R90") (pin "2") (pinfunction "2_2") (pintype "passive"))
      (node (ref "Y16") (pin "2") (pinfunction "E_2") (pintype "passive"))
    )
    (net (code "120") (name "Net-(Y17-B)") (class "Default")
      (node (ref "R77") (pin "2") (pinfunction "2_2") (pintype "passive"))
      (node (ref "Y17") (pin "1") (pinfunction "B_1") (pintype "passive"))
    )
    (net (code "121") (name "Net-(Y17-C)") (class "Default")
      (node (ref "R73") (pin "2") (pinfunction "2_2") (pintype "passive"))
      (node (ref "Y17") (pin "3") (pinfunction "C_3") (pintype "passive"))
    )
    (net (code "122") (name "Net-(Y17-E)") (class "Default")
      (node (ref "R91") (pin "2") (pinfunction "2_2") (pintype "passive"))
      (node (ref "Y17") (pin "2") (pinfunction "E_2") (pintype "passive"))
    )
    (net (code "123") (name "Net-(Y18-B)") (class "Default")
      (node (ref "R98") (pin "1") (pinfunction "1_1") (pintype "passive"))
      (node (ref "Y18") (pin "1") (pinfunction "B_1") (pintype "passive"))
    )
    (net (code "124") (name "Net-(Y19-B)") (class "Default")
      (node (ref "R103") (pin "1") (pinfunction "1_1") (pintype "passive"))
      (node (ref "Y19") (pin "1") (pinfunction "B_1") (pintype "passive"))
    )
    (net (code "125") (name "Net-(Y20-B)") (class "Default")
      (node (ref "R104") (pin "1") (pinfunction "1_1") (pintype "passive"))
      (node (ref "Y20") (pin "1") (pinfunction "B_1") (pintype "passive"))
    )
    (net (code "126") (name "Net-(Y21-B)") (class "Default")
      (node (ref "R105") (pin "2") (pinfunction "2_2") (pintype "passive"))
      (node (ref "Y21") (pin "1") (pinfunction "B_1") (pintype "passive"))
    )
    (net (code "127") (name "Net-(Y21-C)") (class "Default")
      (node (ref "R46") (pin "2") (pinfunction "2_2") (pintype "passive"))
      (node (ref "Y21") (pin "3") (pinfunction "C_3") (pintype "passive"))
    )
    (net (code "128") (name "Net-(Y21-E)") (class "Default")
      (node (ref "R108") (pin "2") (pinfunction "2_2") (pintype "passive"))
      (node (ref "Y21") (pin "2") (pinfunction "E_2") (pintype "passive"))
    )
    (net (code "129") (name "Net-(Y22-B)") (class "Default")
      (node (ref "R106") (pin "1") (pinfunction "1_1") (pintype "passive"))
      (node (ref "Y22") (pin "1") (pinfunction "B_1") (pintype "passive"))
    )
    (net (code "130") (name "Net-(Y23-B)") (class "Default")
      (node (ref "R107") (pin "1") (pinfunction "1_1") (pintype "passive"))
      (node (ref "Y23") (pin "1") (pinfunction "B_1") (pintype "passive"))
    )
    (net (code "131") (name "Net-(Y24-B)") (class "Default")
      (node (ref "R110") (pin "2") (pinfunction "2_2") (pintype "passive"))
      (node (ref "Y24") (pin "1") (pinfunction "B_1") (pintype "passive"))
    )
    (net (code "132") (name "Net-(Y24-C)") (class "Default")
      (node (ref "R86") (pin "2") (pinfunction "2_2") (pintype "passive"))
      (node (ref "Y24") (pin "3") (pinfunction "C_3") (pintype "passive"))
    )
    (net (code "133") (name "Net-(Y24-E)") (class "Default")
      (node (ref "R114") (pin "2") (pinfunction "2_2") (pintype "passive"))
      (node (ref "Y24") (pin "2") (pinfunction "E_2") (pintype "passive"))
    )
    (net (code "134") (name "Net-(Y25-B)") (class "Default")
      (node (ref "R111") (pin "2") (pinfunction "2_2") (pintype "passive"))
      (node (ref "Y25") (pin "1") (pinfunction "B_1") (pintype "passive"))
    )
    (net (code "135") (name "Net-(Y25-C)") (class "Default")
      (node (ref "R87") (pin "2") (pinfunction "2_2") (pintype "passive"))
      (node (ref "Y25") (pin "3") (pinfunction "C_3") (pintype "passive"))
    )
    (net (code "136") (name "Net-(Y25-E)") (class "Default")
      (node (ref "R115") (pin "2") (pinfunction "2_2") (pintype "passive"))
      (node (ref "Y25") (pin "2") (pinfunction "E_2") (pintype "passive"))
    )
    (net (code "137") (name "Net-(Y26-B)") (class "Default")
      (node (ref "R112") (pin "2") (pinfunction "2_2") (pintype "passive"))
      (node (ref "Y26") (pin "1") (pinfunction "B_1") (pintype "passive"))
    )
    (net (code "138") (name "Net-(Y26-C)") (class "Default")
      (node (ref "R89") (pin "2") (pinfunction "2_2") (pintype "passive"))
      (node (ref "Y26") (pin "3") (pinfunction "C_3") (pintype "passive"))
    )
    (net (code "139") (name "Net-(Y26-E)") (class "Default")
      (node (ref "R116") (pin "2") (pinfunction "2_2") (pintype "passive"))
      (node (ref "Y26") (pin "2") (pinfunction "E_2") (pintype "passive"))
    )
    (net (code "140") (name "Net-(Y27-B)") (class "Default")
      (node (ref "R113") (pin "2") (pinfunction "2_2") (pintype "passive"))
      (node (ref "Y27") (pin "1") (pinfunction "B_1") (pintype "passive"))
    )
    (net (code "141") (name "Net-(Y27-C)") (class "Default")
      (node (ref "R84") (pin "2") (pinfunction "2_2") (pintype "passive"))
      (node (ref "Y27") (pin "3") (pinfunction "C_3") (pintype "passive"))
    )
    (net (code "142") (name "Net-(Y27-E)") (class "Default")
      (node (ref "R118") (pin "2") (pinfunction "2_2") (pintype "passive"))
      (node (ref "Y27") (pin "2") (pinfunction "E_2") (pintype "passive"))
    )
    (net (code "143") (name "Net-(Y28-B)") (class "Default")
      (node (ref "R26") (pin "2") (pinfunction "2_2") (pintype "passive"))
      (node (ref "Y28") (pin "1") (pinfunction "B_1") (pintype "passive"))
      (node (ref "Y8") (pin "3") (pinfunction "C_3") (pintype "passive"))
    )
    (net (code "144") (name "Net-(Y29-B)") (class "Default")
      (node (ref "R120") (pin "1") (pinfunction "1_1") (pintype "passive"))
      (node (ref "Y29") (pin "1") (pinfunction "B_1") (pintype "passive"))
      (node (ref "Y9") (pin "3") (pinfunction "C_3") (pintype "passive"))
    )
    (net (code "145") (name "Net-(Y31-B)") (class "Default")
      (node (ref "R28") (pin "1") (pinfunction "1_1") (pintype "passive"))
      (node (ref "Y31") (pin "1") (pinfunction "B_1") (pintype "passive"))
    )
    (net (code "146") (name "Net-(Y32-B)") (class "Default")
      (node (ref "R62") (pin "2") (pinfunction "2_2") (pintype "passive"))
      (node (ref "Y32") (pin "1") (pinfunction "B_1") (pintype "passive"))
    )
    (net (code "147") (name "Net-(Y32-C)") (class "Default")
      (node (ref "R82") (pin "2") (pinfunction "2_2") (pintype "passive"))
      (node (ref "Y32") (pin "3") (pinfunction "C_3") (pintype "passive"))
    )
    (net (code "148") (name "Net-(Y32-E)") (class "Default")
      (node (ref "R64") (pin "2") (pinfunction "2_2") (pintype "passive"))
      (node (ref "Y32") (pin "2") (pinfunction "E_2") (pintype "passive"))
    )
    (net (code "149") (name "unconnected-(U3-BOOT0-Pad44)") (class "Default")
      (node (ref "U3") (pin "44") (pinfunction "BOOT0_44") (pintype "passive"))
    )
    (net (code "150") (name "unconnected-(U3-PA2-Pad12)") (class "Default")
      (node (ref "U3") (pin "12") (pinfunction "PA2_12") (pintype "passive"))
    )
    (net (code "151") (name "unconnected-(U3-PA3-Pad13)") (class "Default")
      (node (ref "U3") (pin "13") (pinfunction "PA3_13") (pintype "passive"))
    )
    (net (code "152") (name "unconnected-(U3-PA4-Pad14)") (class "Default")
      (node (ref "U3") (pin "14") (pinfunction "PA4_14") (pintype "passive"))
    )
    (net (code "153") (name "unconnected-(U3-PA9-Pad30)") (class "Default")
      (node (ref "U3") (pin "30") (pinfunction "PA9_30") (pintype "passive"))
    )
    (net (code "154") (name "unconnected-(U3-PA10-Pad31)") (class "Default")
      (node (ref "U3") (pin "31") (pinfunction "PA10_31") (pintype "passive"))
    )
    (net (code "155") (name "unconnected-(U3-PA11-Pad32)") (class "Default")
      (node (ref "U3") (pin "32") (pinfunction "PA11_32") (pintype "passive"))
    )
    (net (code "156") (name "unconnected-(U3-PA12-Pad33)") (class "Default")
      (node (ref "U3") (pin "33") (pinfunction "PA12_33") (pintype "passive"))
    )
    (net (code "157") (name "unconnected-(U3-PB9-Pad46)") (class "Default")
      (node (ref "U3") (pin "46") (pinfunction "PB9_46") (pintype "passive"))
    )
  )
)
